# LED_Array.net
KiCad netlist of a schematic drawn in EAGLE
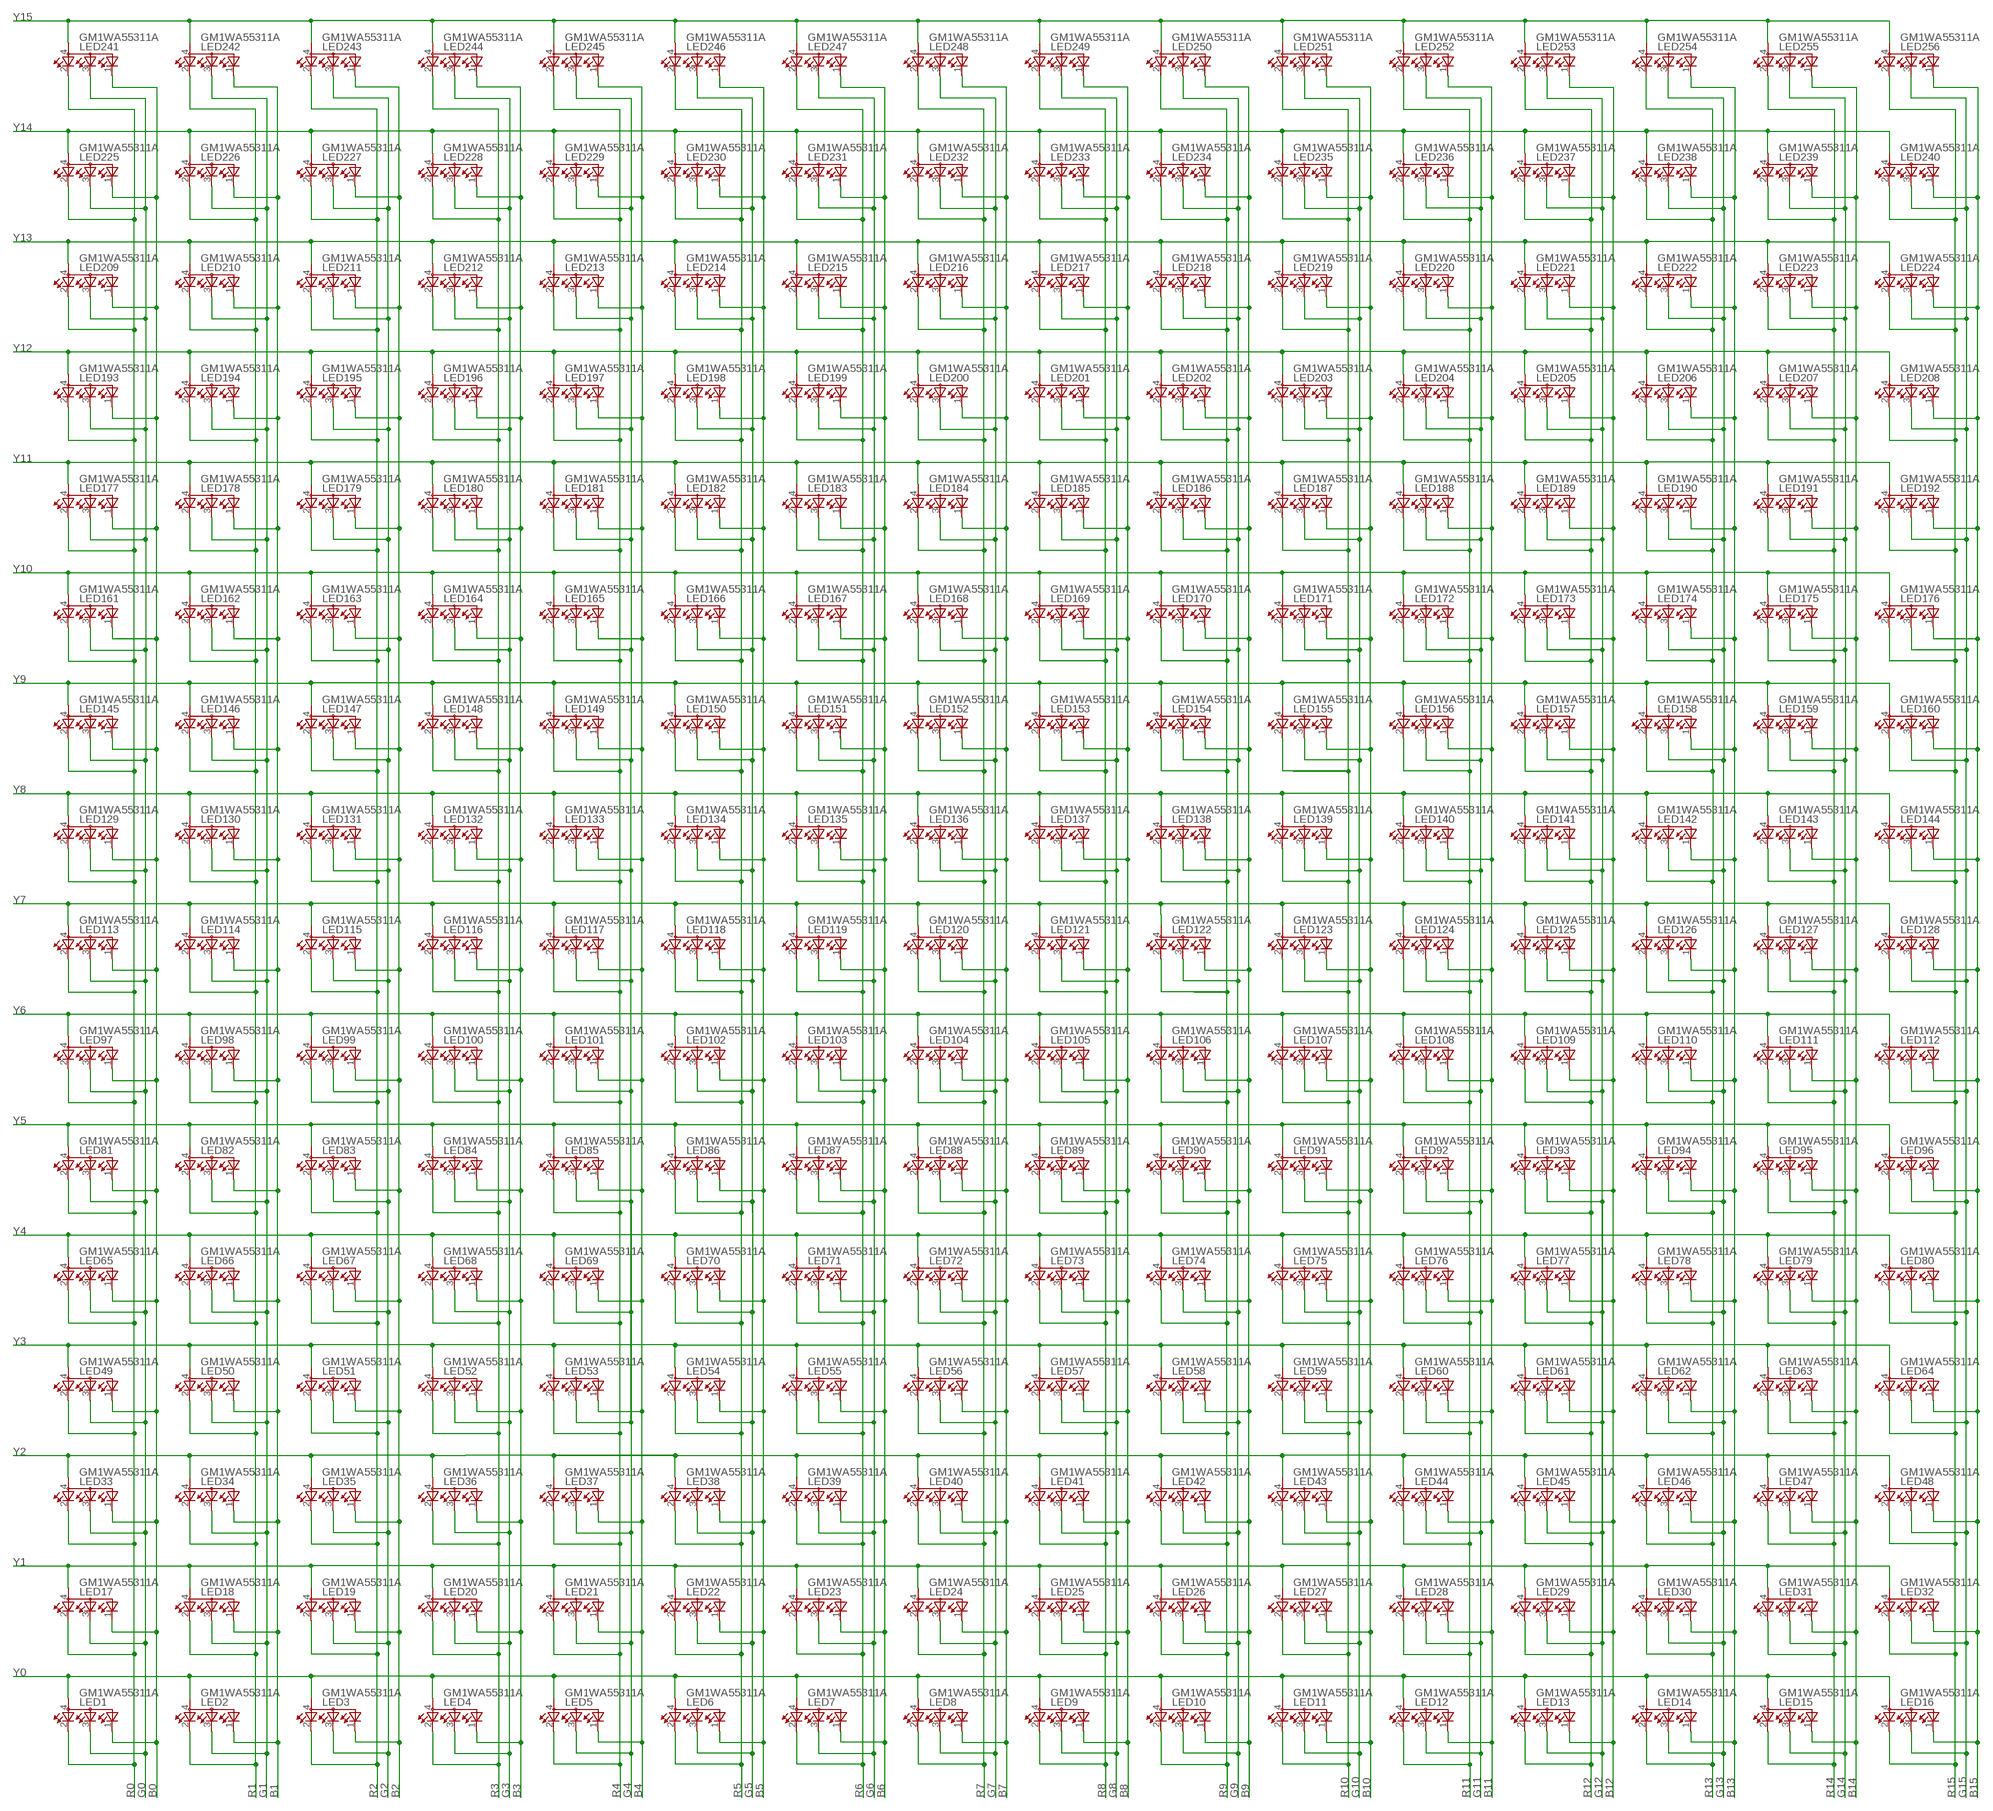
[diagram p0: schematic, sheet 1]

(export (version "E")
  (design (tool "Eeschema 10.0.6"))
  (components
    (comp (ref "LED1")
      (value "GM1WA55311A")
      (footprint "eagle-import:GM1WA55311A")
      (libsource (lib "eagle-import") (part "GM1WA55311A"))
    )
    (comp (ref "LED2")
      (value "GM1WA55311A")
      (footprint "eagle-import:GM1WA55311A")
      (libsource (lib "eagle-import") (part "GM1WA55311A"))
    )
    (comp (ref "LED3")
      (value "GM1WA55311A")
      (footprint "eagle-import:GM1WA55311A")
      (libsource (lib "eagle-import") (part "GM1WA55311A"))
    )
    (comp (ref "LED4")
      (value "GM1WA55311A")
      (footprint "eagle-import:GM1WA55311A")
      (libsource (lib "eagle-import") (part "GM1WA55311A"))
    )
    (comp (ref "LED5")
      (value "GM1WA55311A")
      (footprint "eagle-import:GM1WA55311A")
      (libsource (lib "eagle-import") (part "GM1WA55311A"))
    )
    (comp (ref "LED6")
      (value "GM1WA55311A")
      (footprint "eagle-import:GM1WA55311A")
      (libsource (lib "eagle-import") (part "GM1WA55311A"))
    )
    (comp (ref "LED7")
      (value "GM1WA55311A")
      (footprint "eagle-import:GM1WA55311A")
      (libsource (lib "eagle-import") (part "GM1WA55311A"))
    )
    (comp (ref "LED8")
      (value "GM1WA55311A")
      (footprint "eagle-import:GM1WA55311A")
      (libsource (lib "eagle-import") (part "GM1WA55311A"))
    )
    (comp (ref "LED9")
      (value "GM1WA55311A")
      (footprint "eagle-import:GM1WA55311A")
      (libsource (lib "eagle-import") (part "GM1WA55311A"))
    )
    (comp (ref "LED10")
      (value "GM1WA55311A")
      (footprint "eagle-import:GM1WA55311A")
      (libsource (lib "eagle-import") (part "GM1WA55311A"))
    )
    (comp (ref "LED11")
      (value "GM1WA55311A")
      (footprint "eagle-import:GM1WA55311A")
      (libsource (lib "eagle-import") (part "GM1WA55311A"))
    )
    (comp (ref "LED12")
      (value "GM1WA55311A")
      (footprint "eagle-import:GM1WA55311A")
      (libsource (lib "eagle-import") (part "GM1WA55311A"))
    )
    (comp (ref "LED13")
      (value "GM1WA55311A")
      (footprint "eagle-import:GM1WA55311A")
      (libsource (lib "eagle-import") (part "GM1WA55311A"))
    )
    (comp (ref "LED14")
      (value "GM1WA55311A")
      (footprint "eagle-import:GM1WA55311A")
      (libsource (lib "eagle-import") (part "GM1WA55311A"))
    )
    (comp (ref "LED15")
      (value "GM1WA55311A")
      (footprint "eagle-import:GM1WA55311A")
      (libsource (lib "eagle-import") (part "GM1WA55311A"))
    )
    (comp (ref "LED16")
      (value "GM1WA55311A")
      (footprint "eagle-import:GM1WA55311A")
      (libsource (lib "eagle-import") (part "GM1WA55311A"))
    )
    (comp (ref "LED17")
      (value "GM1WA55311A")
      (footprint "eagle-import:GM1WA55311A")
      (libsource (lib "eagle-import") (part "GM1WA55311A"))
    )
    (comp (ref "LED18")
      (value "GM1WA55311A")
      (footprint "eagle-import:GM1WA55311A")
      (libsource (lib "eagle-import") (part "GM1WA55311A"))
    )
    (comp (ref "LED19")
      (value "GM1WA55311A")
      (footprint "eagle-import:GM1WA55311A")
      (libsource (lib "eagle-import") (part "GM1WA55311A"))
    )
    (comp (ref "LED20")
      (value "GM1WA55311A")
      (footprint "eagle-import:GM1WA55311A")
      (libsource (lib "eagle-import") (part "GM1WA55311A"))
    )
    (comp (ref "LED21")
      (value "GM1WA55311A")
      (footprint "eagle-import:GM1WA55311A")
      (libsource (lib "eagle-import") (part "GM1WA55311A"))
    )
    (comp (ref "LED22")
      (value "GM1WA55311A")
      (footprint "eagle-import:GM1WA55311A")
      (libsource (lib "eagle-import") (part "GM1WA55311A"))
    )
    (comp (ref "LED23")
      (value "GM1WA55311A")
      (footprint "eagle-import:GM1WA55311A")
      (libsource (lib "eagle-import") (part "GM1WA55311A"))
    )
    (comp (ref "LED24")
      (value "GM1WA55311A")
      (footprint "eagle-import:GM1WA55311A")
      (libsource (lib "eagle-import") (part "GM1WA55311A"))
    )
    (comp (ref "LED25")
      (value "GM1WA55311A")
      (footprint "eagle-import:GM1WA55311A")
      (libsource (lib "eagle-import") (part "GM1WA55311A"))
    )
    (comp (ref "LED26")
      (value "GM1WA55311A")
      (footprint "eagle-import:GM1WA55311A")
      (libsource (lib "eagle-import") (part "GM1WA55311A"))
    )
    (comp (ref "LED27")
      (value "GM1WA55311A")
      (footprint "eagle-import:GM1WA55311A")
      (libsource (lib "eagle-import") (part "GM1WA55311A"))
    )
    (comp (ref "LED28")
      (value "GM1WA55311A")
      (footprint "eagle-import:GM1WA55311A")
      (libsource (lib "eagle-import") (part "GM1WA55311A"))
    )
    (comp (ref "LED29")
      (value "GM1WA55311A")
      (footprint "eagle-import:GM1WA55311A")
      (libsource (lib "eagle-import") (part "GM1WA55311A"))
    )
    (comp (ref "LED30")
      (value "GM1WA55311A")
      (footprint "eagle-import:GM1WA55311A")
      (libsource (lib "eagle-import") (part "GM1WA55311A"))
    )
    (comp (ref "LED31")
      (value "GM1WA55311A")
      (footprint "eagle-import:GM1WA55311A")
      (libsource (lib "eagle-import") (part "GM1WA55311A"))
    )
    (comp (ref "LED32")
      (value "GM1WA55311A")
      (footprint "eagle-import:GM1WA55311A")
      (libsource (lib "eagle-import") (part "GM1WA55311A"))
    )
    (comp (ref "LED33")
      (value "GM1WA55311A")
      (footprint "eagle-import:GM1WA55311A")
      (libsource (lib "eagle-import") (part "GM1WA55311A"))
    )
    (comp (ref "LED34")
      (value "GM1WA55311A")
      (footprint "eagle-import:GM1WA55311A")
      (libsource (lib "eagle-import") (part "GM1WA55311A"))
    )
    (comp (ref "LED35")
      (value "GM1WA55311A")
      (footprint "eagle-import:GM1WA55311A")
      (libsource (lib "eagle-import") (part "GM1WA55311A"))
    )
    (comp (ref "LED36")
      (value "GM1WA55311A")
      (footprint "eagle-import:GM1WA55311A")
      (libsource (lib "eagle-import") (part "GM1WA55311A"))
    )
    (comp (ref "LED37")
      (value "GM1WA55311A")
      (footprint "eagle-import:GM1WA55311A")
      (libsource (lib "eagle-import") (part "GM1WA55311A"))
    )
    (comp (ref "LED38")
      (value "GM1WA55311A")
      (footprint "eagle-import:GM1WA55311A")
      (libsource (lib "eagle-import") (part "GM1WA55311A"))
    )
    (comp (ref "LED39")
      (value "GM1WA55311A")
      (footprint "eagle-import:GM1WA55311A")
      (libsource (lib "eagle-import") (part "GM1WA55311A"))
    )
    (comp (ref "LED40")
      (value "GM1WA55311A")
      (footprint "eagle-import:GM1WA55311A")
      (libsource (lib "eagle-import") (part "GM1WA55311A"))
    )
    (comp (ref "LED41")
      (value "GM1WA55311A")
      (footprint "eagle-import:GM1WA55311A")
      (libsource (lib "eagle-import") (part "GM1WA55311A"))
    )
    (comp (ref "LED42")
      (value "GM1WA55311A")
      (footprint "eagle-import:GM1WA55311A")
      (libsource (lib "eagle-import") (part "GM1WA55311A"))
    )
    (comp (ref "LED43")
      (value "GM1WA55311A")
      (footprint "eagle-import:GM1WA55311A")
      (libsource (lib "eagle-import") (part "GM1WA55311A"))
    )
    (comp (ref "LED44")
      (value "GM1WA55311A")
      (footprint "eagle-import:GM1WA55311A")
      (libsource (lib "eagle-import") (part "GM1WA55311A"))
    )
    (comp (ref "LED45")
      (value "GM1WA55311A")
      (footprint "eagle-import:GM1WA55311A")
      (libsource (lib "eagle-import") (part "GM1WA55311A"))
    )
    (comp (ref "LED46")
      (value "GM1WA55311A")
      (footprint "eagle-import:GM1WA55311A")
      (libsource (lib "eagle-import") (part "GM1WA55311A"))
    )
    (comp (ref "LED47")
      (value "GM1WA55311A")
      (footprint "eagle-import:GM1WA55311A")
      (libsource (lib "eagle-import") (part "GM1WA55311A"))
    )
    (comp (ref "LED48")
      (value "GM1WA55311A")
      (footprint "eagle-import:GM1WA55311A")
      (libsource (lib "eagle-import") (part "GM1WA55311A"))
    )
    (comp (ref "LED49")
      (value "GM1WA55311A")
      (footprint "eagle-import:GM1WA55311A")
      (libsource (lib "eagle-import") (part "GM1WA55311A"))
    )
    (comp (ref "LED50")
      (value "GM1WA55311A")
      (footprint "eagle-import:GM1WA55311A")
      (libsource (lib "eagle-import") (part "GM1WA55311A"))
    )
    (comp (ref "LED51")
      (value "GM1WA55311A")
      (footprint "eagle-import:GM1WA55311A")
      (libsource (lib "eagle-import") (part "GM1WA55311A"))
    )
    (comp (ref "LED52")
      (value "GM1WA55311A")
      (footprint "eagle-import:GM1WA55311A")
      (libsource (lib "eagle-import") (part "GM1WA55311A"))
    )
    (comp (ref "LED53")
      (value "GM1WA55311A")
      (footprint "eagle-import:GM1WA55311A")
      (libsource (lib "eagle-import") (part "GM1WA55311A"))
    )
    (comp (ref "LED54")
      (value "GM1WA55311A")
      (footprint "eagle-import:GM1WA55311A")
      (libsource (lib "eagle-import") (part "GM1WA55311A"))
    )
    (comp (ref "LED55")
      (value "GM1WA55311A")
      (footprint "eagle-import:GM1WA55311A")
      (libsource (lib "eagle-import") (part "GM1WA55311A"))
    )
    (comp (ref "LED56")
      (value "GM1WA55311A")
      (footprint "eagle-import:GM1WA55311A")
      (libsource (lib "eagle-import") (part "GM1WA55311A"))
    )
    (comp (ref "LED57")
      (value "GM1WA55311A")
      (footprint "eagle-import:GM1WA55311A")
      (libsource (lib "eagle-import") (part "GM1WA55311A"))
    )
    (comp (ref "LED58")
      (value "GM1WA55311A")
      (footprint "eagle-import:GM1WA55311A")
      (libsource (lib "eagle-import") (part "GM1WA55311A"))
    )
    (comp (ref "LED59")
      (value "GM1WA55311A")
      (footprint "eagle-import:GM1WA55311A")
      (libsource (lib "eagle-import") (part "GM1WA55311A"))
    )
    (comp (ref "LED60")
      (value "GM1WA55311A")
      (footprint "eagle-import:GM1WA55311A")
      (libsource (lib "eagle-import") (part "GM1WA55311A"))
    )
    (comp (ref "LED61")
      (value "GM1WA55311A")
      (footprint "eagle-import:GM1WA55311A")
      (libsource (lib "eagle-import") (part "GM1WA55311A"))
    )
    (comp (ref "LED62")
      (value "GM1WA55311A")
      (footprint "eagle-import:GM1WA55311A")
      (libsource (lib "eagle-import") (part "GM1WA55311A"))
    )
    (comp (ref "LED63")
      (value "GM1WA55311A")
      (footprint "eagle-import:GM1WA55311A")
      (libsource (lib "eagle-import") (part "GM1WA55311A"))
    )
    (comp (ref "LED64")
      (value "GM1WA55311A")
      (footprint "eagle-import:GM1WA55311A")
      (libsource (lib "eagle-import") (part "GM1WA55311A"))
    )
    (comp (ref "LED65")
      (value "GM1WA55311A")
      (footprint "eagle-import:GM1WA55311A")
      (libsource (lib "eagle-import") (part "GM1WA55311A"))
    )
    (comp (ref "LED66")
      (value "GM1WA55311A")
      (footprint "eagle-import:GM1WA55311A")
      (libsource (lib "eagle-import") (part "GM1WA55311A"))
    )
    (comp (ref "LED67")
      (value "GM1WA55311A")
      (footprint "eagle-import:GM1WA55311A")
      (libsource (lib "eagle-import") (part "GM1WA55311A"))
    )
    (comp (ref "LED68")
      (value "GM1WA55311A")
      (footprint "eagle-import:GM1WA55311A")
      (libsource (lib "eagle-import") (part "GM1WA55311A"))
    )
    (comp (ref "LED69")
      (value "GM1WA55311A")
      (footprint "eagle-import:GM1WA55311A")
      (libsource (lib "eagle-import") (part "GM1WA55311A"))
    )
    (comp (ref "LED70")
      (value "GM1WA55311A")
      (footprint "eagle-import:GM1WA55311A")
      (libsource (lib "eagle-import") (part "GM1WA55311A"))
    )
    (comp (ref "LED71")
      (value "GM1WA55311A")
      (footprint "eagle-import:GM1WA55311A")
      (libsource (lib "eagle-import") (part "GM1WA55311A"))
    )
    (comp (ref "LED72")
      (value "GM1WA55311A")
      (footprint "eagle-import:GM1WA55311A")
      (libsource (lib "eagle-import") (part "GM1WA55311A"))
    )
    (comp (ref "LED73")
      (value "GM1WA55311A")
      (footprint "eagle-import:GM1WA55311A")
      (libsource (lib "eagle-import") (part "GM1WA55311A"))
    )
    (comp (ref "LED74")
      (value "GM1WA55311A")
      (footprint "eagle-import:GM1WA55311A")
      (libsource (lib "eagle-import") (part "GM1WA55311A"))
    )
    (comp (ref "LED75")
      (value "GM1WA55311A")
      (footprint "eagle-import:GM1WA55311A")
      (libsource (lib "eagle-import") (part "GM1WA55311A"))
    )
    (comp (ref "LED76")
      (value "GM1WA55311A")
      (footprint "eagle-import:GM1WA55311A")
      (libsource (lib "eagle-import") (part "GM1WA55311A"))
    )
    (comp (ref "LED77")
      (value "GM1WA55311A")
      (footprint "eagle-import:GM1WA55311A")
      (libsource (lib "eagle-import") (part "GM1WA55311A"))
    )
    (comp (ref "LED78")
      (value "GM1WA55311A")
      (footprint "eagle-import:GM1WA55311A")
      (libsource (lib "eagle-import") (part "GM1WA55311A"))
    )
    (comp (ref "LED79")
      (value "GM1WA55311A")
      (footprint "eagle-import:GM1WA55311A")
      (libsource (lib "eagle-import") (part "GM1WA55311A"))
    )
    (comp (ref "LED80")
      (value "GM1WA55311A")
      (footprint "eagle-import:GM1WA55311A")
      (libsource (lib "eagle-import") (part "GM1WA55311A"))
    )
    (comp (ref "LED81")
      (value "GM1WA55311A")
      (footprint "eagle-import:GM1WA55311A")
      (libsource (lib "eagle-import") (part "GM1WA55311A"))
    )
    (comp (ref "LED82")
      (value "GM1WA55311A")
      (footprint "eagle-import:GM1WA55311A")
      (libsource (lib "eagle-import") (part "GM1WA55311A"))
    )
    (comp (ref "LED83")
      (value "GM1WA55311A")
      (footprint "eagle-import:GM1WA55311A")
      (libsource (lib "eagle-import") (part "GM1WA55311A"))
    )
    (comp (ref "LED84")
      (value "GM1WA55311A")
      (footprint "eagle-import:GM1WA55311A")
      (libsource (lib "eagle-import") (part "GM1WA55311A"))
    )
    (comp (ref "LED85")
      (value "GM1WA55311A")
      (footprint "eagle-import:GM1WA55311A")
      (libsource (lib "eagle-import") (part "GM1WA55311A"))
    )
    (comp (ref "LED86")
      (value "GM1WA55311A")
      (footprint "eagle-import:GM1WA55311A")
      (libsource (lib "eagle-import") (part "GM1WA55311A"))
    )
    (comp (ref "LED87")
      (value "GM1WA55311A")
      (footprint "eagle-import:GM1WA55311A")
      (libsource (lib "eagle-import") (part "GM1WA55311A"))
    )
    (comp (ref "LED88")
      (value "GM1WA55311A")
      (footprint "eagle-import:GM1WA55311A")
      (libsource (lib "eagle-import") (part "GM1WA55311A"))
    )
    (comp (ref "LED89")
      (value "GM1WA55311A")
      (footprint "eagle-import:GM1WA55311A")
      (libsource (lib "eagle-import") (part "GM1WA55311A"))
    )
    (comp (ref "LED90")
      (value "GM1WA55311A")
      (footprint "eagle-import:GM1WA55311A")
      (libsource (lib "eagle-import") (part "GM1WA55311A"))
    )
    (comp (ref "LED91")
      (value "GM1WA55311A")
      (footprint "eagle-import:GM1WA55311A")
      (libsource (lib "eagle-import") (part "GM1WA55311A"))
    )
    (comp (ref "LED92")
      (value "GM1WA55311A")
      (footprint "eagle-import:GM1WA55311A")
      (libsource (lib "eagle-import") (part "GM1WA55311A"))
    )
    (comp (ref "LED93")
      (value "GM1WA55311A")
      (footprint "eagle-import:GM1WA55311A")
      (libsource (lib "eagle-import") (part "GM1WA55311A"))
    )
    (comp (ref "LED94")
      (value "GM1WA55311A")
      (footprint "eagle-import:GM1WA55311A")
      (libsource (lib "eagle-import") (part "GM1WA55311A"))
    )
    (comp (ref "LED95")
      (value "GM1WA55311A")
      (footprint "eagle-import:GM1WA55311A")
      (libsource (lib "eagle-import") (part "GM1WA55311A"))
    )
    (comp (ref "LED96")
      (value "GM1WA55311A")
      (footprint "eagle-import:GM1WA55311A")
      (libsource (lib "eagle-import") (part "GM1WA55311A"))
    )
    (comp (ref "LED97")
      (value "GM1WA55311A")
      (footprint "eagle-import:GM1WA55311A")
      (libsource (lib "eagle-import") (part "GM1WA55311A"))
    )
    (comp (ref "LED98")
      (value "GM1WA55311A")
      (footprint "eagle-import:GM1WA55311A")
      (libsource (lib "eagle-import") (part "GM1WA55311A"))
    )
    (comp (ref "LED99")
      (value "GM1WA55311A")
      (footprint "eagle-import:GM1WA55311A")
      (libsource (lib "eagle-import") (part "GM1WA55311A"))
    )
    (comp (ref "LED100")
      (value "GM1WA55311A")
      (footprint "eagle-import:GM1WA55311A")
      (libsource (lib "eagle-import") (part "GM1WA55311A"))
    )
    (comp (ref "LED101")
      (value "GM1WA55311A")
      (footprint "eagle-import:GM1WA55311A")
      (libsource (lib "eagle-import") (part "GM1WA55311A"))
    )
    (comp (ref "LED102")
      (value "GM1WA55311A")
      (footprint "eagle-import:GM1WA55311A")
      (libsource (lib "eagle-import") (part "GM1WA55311A"))
    )
    (comp (ref "LED103")
      (value "GM1WA55311A")
      (footprint "eagle-import:GM1WA55311A")
      (libsource (lib "eagle-import") (part "GM1WA55311A"))
    )
    (comp (ref "LED104")
      (value "GM1WA55311A")
      (footprint "eagle-import:GM1WA55311A")
      (libsource (lib "eagle-import") (part "GM1WA55311A"))
    )
    (comp (ref "LED105")
      (value "GM1WA55311A")
      (footprint "eagle-import:GM1WA55311A")
      (libsource (lib "eagle-import") (part "GM1WA55311A"))
    )
    (comp (ref "LED106")
      (value "GM1WA55311A")
      (footprint "eagle-import:GM1WA55311A")
      (libsource (lib "eagle-import") (part "GM1WA55311A"))
    )
    (comp (ref "LED107")
      (value "GM1WA55311A")
      (footprint "eagle-import:GM1WA55311A")
      (libsource (lib "eagle-import") (part "GM1WA55311A"))
    )
    (comp (ref "LED108")
      (value "GM1WA55311A")
      (footprint "eagle-import:GM1WA55311A")
      (libsource (lib "eagle-import") (part "GM1WA55311A"))
    )
    (comp (ref "LED109")
      (value "GM1WA55311A")
      (footprint "eagle-import:GM1WA55311A")
      (libsource (lib "eagle-import") (part "GM1WA55311A"))
    )
    (comp (ref "LED110")
      (value "GM1WA55311A")
      (footprint "eagle-import:GM1WA55311A")
      (libsource (lib "eagle-import") (part "GM1WA55311A"))
    )
    (comp (ref "LED111")
      (value "GM1WA55311A")
      (footprint "eagle-import:GM1WA55311A")
      (libsource (lib "eagle-import") (part "GM1WA55311A"))
    )
    (comp (ref "LED112")
      (value "GM1WA55311A")
      (footprint "eagle-import:GM1WA55311A")
      (libsource (lib "eagle-import") (part "GM1WA55311A"))
    )
    (comp (ref "LED113")
      (value "GM1WA55311A")
      (footprint "eagle-import:GM1WA55311A")
      (libsource (lib "eagle-import") (part "GM1WA55311A"))
    )
    (comp (ref "LED114")
      (value "GM1WA55311A")
      (footprint "eagle-import:GM1WA55311A")
      (libsource (lib "eagle-import") (part "GM1WA55311A"))
    )
    (comp (ref "LED115")
      (value "GM1WA55311A")
      (footprint "eagle-import:GM1WA55311A")
      (libsource (lib "eagle-import") (part "GM1WA55311A"))
    )
    (comp (ref "LED116")
      (value "GM1WA55311A")
      (footprint "eagle-import:GM1WA55311A")
      (libsource (lib "eagle-import") (part "GM1WA55311A"))
    )
    (comp (ref "LED117")
      (value "GM1WA55311A")
      (footprint "eagle-import:GM1WA55311A")
      (libsource (lib "eagle-import") (part "GM1WA55311A"))
    )
    (comp (ref "LED118")
      (value "GM1WA55311A")
      (footprint "eagle-import:GM1WA55311A")
      (libsource (lib "eagle-import") (part "GM1WA55311A"))
    )
    (comp (ref "LED119")
      (value "GM1WA55311A")
      (footprint "eagle-import:GM1WA55311A")
      (libsource (lib "eagle-import") (part "GM1WA55311A"))
    )
    (comp (ref "LED120")
      (value "GM1WA55311A")
      (footprint "eagle-import:GM1WA55311A")
      (libsource (lib "eagle-import") (part "GM1WA55311A"))
    )
    (comp (ref "LED121")
      (value "GM1WA55311A")
      (footprint "eagle-import:GM1WA55311A")
      (libsource (lib "eagle-import") (part "GM1WA55311A"))
    )
    (comp (ref "LED122")
      (value "GM1WA55311A")
      (footprint "eagle-import:GM1WA55311A")
      (libsource (lib "eagle-import") (part "GM1WA55311A"))
    )
    (comp (ref "LED123")
      (value "GM1WA55311A")
      (footprint "eagle-import:GM1WA55311A")
      (libsource (lib "eagle-import") (part "GM1WA55311A"))
    )
    (comp (ref "LED124")
      (value "GM1WA55311A")
      (footprint "eagle-import:GM1WA55311A")
      (libsource (lib "eagle-import") (part "GM1WA55311A"))
    )
    (comp (ref "LED125")
      (value "GM1WA55311A")
      (footprint "eagle-import:GM1WA55311A")
      (libsource (lib "eagle-import") (part "GM1WA55311A"))
    )
    (comp (ref "LED126")
      (value "GM1WA55311A")
      (footprint "eagle-import:GM1WA55311A")
      (libsource (lib "eagle-import") (part "GM1WA55311A"))
    )
    (comp (ref "LED127")
      (value "GM1WA55311A")
      (footprint "eagle-import:GM1WA55311A")
      (libsource (lib "eagle-import") (part "GM1WA55311A"))
    )
    (comp (ref "LED128")
      (value "GM1WA55311A")
      (footprint "eagle-import:GM1WA55311A")
      (libsource (lib "eagle-import") (part "GM1WA55311A"))
    )
    (comp (ref "LED129")
      (value "GM1WA55311A")
      (footprint "eagle-import:GM1WA55311A")
      (libsource (lib "eagle-import") (part "GM1WA55311A"))
    )
    (comp (ref "LED130")
      (value "GM1WA55311A")
      (footprint "eagle-import:GM1WA55311A")
      (libsource (lib "eagle-import") (part "GM1WA55311A"))
    )
    (comp (ref "LED131")
      (value "GM1WA55311A")
      (footprint "eagle-import:GM1WA55311A")
      (libsource (lib "eagle-import") (part "GM1WA55311A"))
    )
    (comp (ref "LED132")
      (value "GM1WA55311A")
      (footprint "eagle-import:GM1WA55311A")
      (libsource (lib "eagle-import") (part "GM1WA55311A"))
    )
    (comp (ref "LED133")
      (value "GM1WA55311A")
      (footprint "eagle-import:GM1WA55311A")
      (libsource (lib "eagle-import") (part "GM1WA55311A"))
    )
    (comp (ref "LED134")
      (value "GM1WA55311A")
      (footprint "eagle-import:GM1WA55311A")
      (libsource (lib "eagle-import") (part "GM1WA55311A"))
    )
    (comp (ref "LED135")
      (value "GM1WA55311A")
      (footprint "eagle-import:GM1WA55311A")
      (libsource (lib "eagle-import") (part "GM1WA55311A"))
    )
    (comp (ref "LED136")
      (value "GM1WA55311A")
      (footprint "eagle-import:GM1WA55311A")
      (libsource (lib "eagle-import") (part "GM1WA55311A"))
    )
    (comp (ref "LED137")
      (value "GM1WA55311A")
      (footprint "eagle-import:GM1WA55311A")
      (libsource (lib "eagle-import") (part "GM1WA55311A"))
    )
    (comp (ref "LED138")
      (value "GM1WA55311A")
      (footprint "eagle-import:GM1WA55311A")
      (libsource (lib "eagle-import") (part "GM1WA55311A"))
    )
    (comp (ref "LED139")
      (value "GM1WA55311A")
      (footprint "eagle-import:GM1WA55311A")
      (libsource (lib "eagle-import") (part "GM1WA55311A"))
    )
    (comp (ref "LED140")
      (value "GM1WA55311A")
      (footprint "eagle-import:GM1WA55311A")
      (libsource (lib "eagle-import") (part "GM1WA55311A"))
    )
    (comp (ref "LED141")
      (value "GM1WA55311A")
      (footprint "eagle-import:GM1WA55311A")
      (libsource (lib "eagle-import") (part "GM1WA55311A"))
    )
    (comp (ref "LED142")
      (value "GM1WA55311A")
      (footprint "eagle-import:GM1WA55311A")
      (libsource (lib "eagle-import") (part "GM1WA55311A"))
    )
    (comp (ref "LED143")
      (value "GM1WA55311A")
      (footprint "eagle-import:GM1WA55311A")
      (libsource (lib "eagle-import") (part "GM1WA55311A"))
    )
    (comp (ref "LED144")
      (value "GM1WA55311A")
      (footprint "eagle-import:GM1WA55311A")
      (libsource (lib "eagle-import") (part "GM1WA55311A"))
    )
    (comp (ref "LED145")
      (value "GM1WA55311A")
      (footprint "eagle-import:GM1WA55311A")
      (libsource (lib "eagle-import") (part "GM1WA55311A"))
    )
    (comp (ref "LED146")
      (value "GM1WA55311A")
      (footprint "eagle-import:GM1WA55311A")
      (libsource (lib "eagle-import") (part "GM1WA55311A"))
    )
    (comp (ref "LED147")
      (value "GM1WA55311A")
      (footprint "eagle-import:GM1WA55311A")
      (libsource (lib "eagle-import") (part "GM1WA55311A"))
    )
    (comp (ref "LED148")
      (value "GM1WA55311A")
      (footprint "eagle-import:GM1WA55311A")
      (libsource (lib "eagle-import") (part "GM1WA55311A"))
    )
    (comp (ref "LED149")
      (value "GM1WA55311A")
      (footprint "eagle-import:GM1WA55311A")
      (libsource (lib "eagle-import") (part "GM1WA55311A"))
    )
    (comp (ref "LED150")
      (value "GM1WA55311A")
      (footprint "eagle-import:GM1WA55311A")
      (libsource (lib "eagle-import") (part "GM1WA55311A"))
    )
    (comp (ref "LED151")
      (value "GM1WA55311A")
      (footprint "eagle-import:GM1WA55311A")
      (libsource (lib "eagle-import") (part "GM1WA55311A"))
    )
    (comp (ref "LED152")
      (value "GM1WA55311A")
      (footprint "eagle-import:GM1WA55311A")
      (libsource (lib "eagle-import") (part "GM1WA55311A"))
    )
    (comp (ref "LED153")
      (value "GM1WA55311A")
      (footprint "eagle-import:GM1WA55311A")
      (libsource (lib "eagle-import") (part "GM1WA55311A"))
    )
    (comp (ref "LED154")
      (value "GM1WA55311A")
      (footprint "eagle-import:GM1WA55311A")
      (libsource (lib "eagle-import") (part "GM1WA55311A"))
    )
    (comp (ref "LED155")
      (value "GM1WA55311A")
      (footprint "eagle-import:GM1WA55311A")
      (libsource (lib "eagle-import") (part "GM1WA55311A"))
    )
    (comp (ref "LED156")
      (value "GM1WA55311A")
      (footprint "eagle-import:GM1WA55311A")
      (libsource (lib "eagle-import") (part "GM1WA55311A"))
    )
    (comp (ref "LED157")
      (value "GM1WA55311A")
      (footprint "eagle-import:GM1WA55311A")
      (libsource (lib "eagle-import") (part "GM1WA55311A"))
    )
    (comp (ref "LED158")
      (value "GM1WA55311A")
      (footprint "eagle-import:GM1WA55311A")
      (libsource (lib "eagle-import") (part "GM1WA55311A"))
    )
    (comp (ref "LED159")
      (value "GM1WA55311A")
      (footprint "eagle-import:GM1WA55311A")
      (libsource (lib "eagle-import") (part "GM1WA55311A"))
    )
    (comp (ref "LED160")
      (value "GM1WA55311A")
      (footprint "eagle-import:GM1WA55311A")
      (libsource (lib "eagle-import") (part "GM1WA55311A"))
    )
    (comp (ref "LED161")
      (value "GM1WA55311A")
      (footprint "eagle-import:GM1WA55311A")
      (libsource (lib "eagle-import") (part "GM1WA55311A"))
    )
    (comp (ref "LED162")
      (value "GM1WA55311A")
      (footprint "eagle-import:GM1WA55311A")
      (libsource (lib "eagle-import") (part "GM1WA55311A"))
    )
    (comp (ref "LED163")
      (value "GM1WA55311A")
      (footprint "eagle-import:GM1WA55311A")
      (libsource (lib "eagle-import") (part "GM1WA55311A"))
    )
    (comp (ref "LED164")
      (value "GM1WA55311A")
      (footprint "eagle-import:GM1WA55311A")
      (libsource (lib "eagle-import") (part "GM1WA55311A"))
    )
    (comp (ref "LED165")
      (value "GM1WA55311A")
      (footprint "eagle-import:GM1WA55311A")
      (libsource (lib "eagle-import") (part "GM1WA55311A"))
    )
    (comp (ref "LED166")
      (value "GM1WA55311A")
      (footprint "eagle-import:GM1WA55311A")
      (libsource (lib "eagle-import") (part "GM1WA55311A"))
    )
    (comp (ref "LED167")
      (value "GM1WA55311A")
      (footprint "eagle-import:GM1WA55311A")
      (libsource (lib "eagle-import") (part "GM1WA55311A"))
    )
    (comp (ref "LED168")
      (value "GM1WA55311A")
      (footprint "eagle-import:GM1WA55311A")
      (libsource (lib "eagle-import") (part "GM1WA55311A"))
    )
    (comp (ref "LED169")
      (value "GM1WA55311A")
      (footprint "eagle-import:GM1WA55311A")
      (libsource (lib "eagle-import") (part "GM1WA55311A"))
    )
    (comp (ref "LED170")
      (value "GM1WA55311A")
      (footprint "eagle-import:GM1WA55311A")
      (libsource (lib "eagle-import") (part "GM1WA55311A"))
    )
    (comp (ref "LED171")
      (value "GM1WA55311A")
      (footprint "eagle-import:GM1WA55311A")
      (libsource (lib "eagle-import") (part "GM1WA55311A"))
    )
    (comp (ref "LED172")
      (value "GM1WA55311A")
      (footprint "eagle-import:GM1WA55311A")
      (libsource (lib "eagle-import") (part "GM1WA55311A"))
    )
    (comp (ref "LED173")
      (value "GM1WA55311A")
      (footprint "eagle-import:GM1WA55311A")
      (libsource (lib "eagle-import") (part "GM1WA55311A"))
    )
    (comp (ref "LED174")
      (value "GM1WA55311A")
      (footprint "eagle-import:GM1WA55311A")
      (libsource (lib "eagle-import") (part "GM1WA55311A"))
    )
    (comp (ref "LED175")
      (value "GM1WA55311A")
      (footprint "eagle-import:GM1WA55311A")
      (libsource (lib "eagle-import") (part "GM1WA55311A"))
    )
    (comp (ref "LED176")
      (value "GM1WA55311A")
      (footprint "eagle-import:GM1WA55311A")
      (libsource (lib "eagle-import") (part "GM1WA55311A"))
    )
    (comp (ref "LED177")
      (value "GM1WA55311A")
      (footprint "eagle-import:GM1WA55311A")
      (libsource (lib "eagle-import") (part "GM1WA55311A"))
    )
    (comp (ref "LED178")
      (value "GM1WA55311A")
      (footprint "eagle-import:GM1WA55311A")
      (libsource (lib "eagle-import") (part "GM1WA55311A"))
    )
    (comp (ref "LED179")
      (value "GM1WA55311A")
      (footprint "eagle-import:GM1WA55311A")
      (libsource (lib "eagle-import") (part "GM1WA55311A"))
    )
    (comp (ref "LED180")
      (value "GM1WA55311A")
      (footprint "eagle-import:GM1WA55311A")
      (libsource (lib "eagle-import") (part "GM1WA55311A"))
    )
    (comp (ref "LED181")
      (value "GM1WA55311A")
      (footprint "eagle-import:GM1WA55311A")
      (libsource (lib "eagle-import") (part "GM1WA55311A"))
    )
    (comp (ref "LED182")
      (value "GM1WA55311A")
      (footprint "eagle-import:GM1WA55311A")
      (libsource (lib "eagle-import") (part "GM1WA55311A"))
    )
    (comp (ref "LED183")
      (value "GM1WA55311A")
      (footprint "eagle-import:GM1WA55311A")
      (libsource (lib "eagle-import") (part "GM1WA55311A"))
    )
    (comp (ref "LED184")
      (value "GM1WA55311A")
      (footprint "eagle-import:GM1WA55311A")
      (libsource (lib "eagle-import") (part "GM1WA55311A"))
    )
    (comp (ref "LED185")
      (value "GM1WA55311A")
      (footprint "eagle-import:GM1WA55311A")
      (libsource (lib "eagle-import") (part "GM1WA55311A"))
    )
    (comp (ref "LED186")
      (value "GM1WA55311A")
      (footprint "eagle-import:GM1WA55311A")
      (libsource (lib "eagle-import") (part "GM1WA55311A"))
    )
    (comp (ref "LED187")
      (value "GM1WA55311A")
      (footprint "eagle-import:GM1WA55311A")
      (libsource (lib "eagle-import") (part "GM1WA55311A"))
    )
    (comp (ref "LED188")
      (value "GM1WA55311A")
      (footprint "eagle-import:GM1WA55311A")
      (libsource (lib "eagle-import") (part "GM1WA55311A"))
    )
    (comp (ref "LED189")
      (value "GM1WA55311A")
      (footprint "eagle-import:GM1WA55311A")
      (libsource (lib "eagle-import") (part "GM1WA55311A"))
    )
    (comp (ref "LED190")
      (value "GM1WA55311A")
      (footprint "eagle-import:GM1WA55311A")
      (libsource (lib "eagle-import") (part "GM1WA55311A"))
    )
    (comp (ref "LED191")
      (value "GM1WA55311A")
      (footprint "eagle-import:GM1WA55311A")
      (libsource (lib "eagle-import") (part "GM1WA55311A"))
    )
    (comp (ref "LED192")
      (value "GM1WA55311A")
      (footprint "eagle-import:GM1WA55311A")
      (libsource (lib "eagle-import") (part "GM1WA55311A"))
    )
    (comp (ref "LED193")
      (value "GM1WA55311A")
      (footprint "eagle-import:GM1WA55311A")
      (libsource (lib "eagle-import") (part "GM1WA55311A"))
    )
    (comp (ref "LED194")
      (value "GM1WA55311A")
      (footprint "eagle-import:GM1WA55311A")
      (libsource (lib "eagle-import") (part "GM1WA55311A"))
    )
    (comp (ref "LED195")
      (value "GM1WA55311A")
      (footprint "eagle-import:GM1WA55311A")
      (libsource (lib "eagle-import") (part "GM1WA55311A"))
    )
    (comp (ref "LED196")
      (value "GM1WA55311A")
      (footprint "eagle-import:GM1WA55311A")
      (libsource (lib "eagle-import") (part "GM1WA55311A"))
    )
    (comp (ref "LED197")
      (value "GM1WA55311A")
      (footprint "eagle-import:GM1WA55311A")
      (libsource (lib "eagle-import") (part "GM1WA55311A"))
    )
    (comp (ref "LED198")
      (value "GM1WA55311A")
      (footprint "eagle-import:GM1WA55311A")
      (libsource (lib "eagle-import") (part "GM1WA55311A"))
    )
    (comp (ref "LED199")
      (value "GM1WA55311A")
      (footprint "eagle-import:GM1WA55311A")
      (libsource (lib "eagle-import") (part "GM1WA55311A"))
    )
    (comp (ref "LED200")
      (value "GM1WA55311A")
      (footprint "eagle-import:GM1WA55311A")
      (libsource (lib "eagle-import") (part "GM1WA55311A"))
    )
    (comp (ref "LED201")
      (value "GM1WA55311A")
      (footprint "eagle-import:GM1WA55311A")
      (libsource (lib "eagle-import") (part "GM1WA55311A"))
    )
    (comp (ref "LED202")
      (value "GM1WA55311A")
      (footprint "eagle-import:GM1WA55311A")
      (libsource (lib "eagle-import") (part "GM1WA55311A"))
    )
    (comp (ref "LED203")
      (value "GM1WA55311A")
      (footprint "eagle-import:GM1WA55311A")
      (libsource (lib "eagle-import") (part "GM1WA55311A"))
    )
    (comp (ref "LED204")
      (value "GM1WA55311A")
      (footprint "eagle-import:GM1WA55311A")
      (libsource (lib "eagle-import") (part "GM1WA55311A"))
    )
    (comp (ref "LED205")
      (value "GM1WA55311A")
      (footprint "eagle-import:GM1WA55311A")
      (libsource (lib "eagle-import") (part "GM1WA55311A"))
    )
    (comp (ref "LED206")
      (value "GM1WA55311A")
      (footprint "eagle-import:GM1WA55311A")
      (libsource (lib "eagle-import") (part "GM1WA55311A"))
    )
    (comp (ref "LED207")
      (value "GM1WA55311A")
      (footprint "eagle-import:GM1WA55311A")
      (libsource (lib "eagle-import") (part "GM1WA55311A"))
    )
    (comp (ref "LED208")
      (value "GM1WA55311A")
      (footprint "eagle-import:GM1WA55311A")
      (libsource (lib "eagle-import") (part "GM1WA55311A"))
    )
    (comp (ref "LED209")
      (value "GM1WA55311A")
      (footprint "eagle-import:GM1WA55311A")
      (libsource (lib "eagle-import") (part "GM1WA55311A"))
    )
    (comp (ref "LED210")
      (value "GM1WA55311A")
      (footprint "eagle-import:GM1WA55311A")
      (libsource (lib "eagle-import") (part "GM1WA55311A"))
    )
    (comp (ref "LED211")
      (value "GM1WA55311A")
      (footprint "eagle-import:GM1WA55311A")
      (libsource (lib "eagle-import") (part "GM1WA55311A"))
    )
    (comp (ref "LED212")
      (value "GM1WA55311A")
      (footprint "eagle-import:GM1WA55311A")
      (libsource (lib "eagle-import") (part "GM1WA55311A"))
    )
    (comp (ref "LED213")
      (value "GM1WA55311A")
      (footprint "eagle-import:GM1WA55311A")
      (libsource (lib "eagle-import") (part "GM1WA55311A"))
    )
    (comp (ref "LED214")
      (value "GM1WA55311A")
      (footprint "eagle-import:GM1WA55311A")
      (libsource (lib "eagle-import") (part "GM1WA55311A"))
    )
    (comp (ref "LED215")
      (value "GM1WA55311A")
      (footprint "eagle-import:GM1WA55311A")
      (libsource (lib "eagle-import") (part "GM1WA55311A"))
    )
    (comp (ref "LED216")
      (value "GM1WA55311A")
      (footprint "eagle-import:GM1WA55311A")
      (libsource (lib "eagle-import") (part "GM1WA55311A"))
    )
    (comp (ref "LED217")
      (value "GM1WA55311A")
      (footprint "eagle-import:GM1WA55311A")
      (libsource (lib "eagle-import") (part "GM1WA55311A"))
    )
    (comp (ref "LED218")
      (value "GM1WA55311A")
      (footprint "eagle-import:GM1WA55311A")
      (libsource (lib "eagle-import") (part "GM1WA55311A"))
    )
    (comp (ref "LED219")
      (value "GM1WA55311A")
      (footprint "eagle-import:GM1WA55311A")
      (libsource (lib "eagle-import") (part "GM1WA55311A"))
    )
    (comp (ref "LED220")
      (value "GM1WA55311A")
      (footprint "eagle-import:GM1WA55311A")
      (libsource (lib "eagle-import") (part "GM1WA55311A"))
    )
    (comp (ref "LED221")
      (value "GM1WA55311A")
      (footprint "eagle-import:GM1WA55311A")
      (libsource (lib "eagle-import") (part "GM1WA55311A"))
    )
    (comp (ref "LED222")
      (value "GM1WA55311A")
      (footprint "eagle-import:GM1WA55311A")
      (libsource (lib "eagle-import") (part "GM1WA55311A"))
    )
    (comp (ref "LED223")
      (value "GM1WA55311A")
      (footprint "eagle-import:GM1WA55311A")
      (libsource (lib "eagle-import") (part "GM1WA55311A"))
    )
    (comp (ref "LED224")
      (value "GM1WA55311A")
      (footprint "eagle-import:GM1WA55311A")
      (libsource (lib "eagle-import") (part "GM1WA55311A"))
    )
    (comp (ref "LED225")
      (value "GM1WA55311A")
      (footprint "eagle-import:GM1WA55311A")
      (libsource (lib "eagle-import") (part "GM1WA55311A"))
    )
    (comp (ref "LED226")
      (value "GM1WA55311A")
      (footprint "eagle-import:GM1WA55311A")
      (libsource (lib "eagle-import") (part "GM1WA55311A"))
    )
    (comp (ref "LED227")
      (value "GM1WA55311A")
      (footprint "eagle-import:GM1WA55311A")
      (libsource (lib "eagle-import") (part "GM1WA55311A"))
    )
    (comp (ref "LED228")
      (value "GM1WA55311A")
      (footprint "eagle-import:GM1WA55311A")
      (libsource (lib "eagle-import") (part "GM1WA55311A"))
    )
    (comp (ref "LED229")
      (value "GM1WA55311A")
      (footprint "eagle-import:GM1WA55311A")
      (libsource (lib "eagle-import") (part "GM1WA55311A"))
    )
    (comp (ref "LED230")
      (value "GM1WA55311A")
      (footprint "eagle-import:GM1WA55311A")
      (libsource (lib "eagle-import") (part "GM1WA55311A"))
    )
    (comp (ref "LED231")
      (value "GM1WA55311A")
      (footprint "eagle-import:GM1WA55311A")
      (libsource (lib "eagle-import") (part "GM1WA55311A"))
    )
    (comp (ref "LED232")
      (value "GM1WA55311A")
      (footprint "eagle-import:GM1WA55311A")
      (libsource (lib "eagle-import") (part "GM1WA55311A"))
    )
    (comp (ref "LED233")
      (value "GM1WA55311A")
      (footprint "eagle-import:GM1WA55311A")
      (libsource (lib "eagle-import") (part "GM1WA55311A"))
    )
    (comp (ref "LED234")
      (value "GM1WA55311A")
      (footprint "eagle-import:GM1WA55311A")
      (libsource (lib "eagle-import") (part "GM1WA55311A"))
    )
    (comp (ref "LED235")
      (value "GM1WA55311A")
      (footprint "eagle-import:GM1WA55311A")
      (libsource (lib "eagle-import") (part "GM1WA55311A"))
    )
    (comp (ref "LED236")
      (value "GM1WA55311A")
      (footprint "eagle-import:GM1WA55311A")
      (libsource (lib "eagle-import") (part "GM1WA55311A"))
    )
    (comp (ref "LED237")
      (value "GM1WA55311A")
      (footprint "eagle-import:GM1WA55311A")
      (libsource (lib "eagle-import") (part "GM1WA55311A"))
    )
    (comp (ref "LED238")
      (value "GM1WA55311A")
      (footprint "eagle-import:GM1WA55311A")
      (libsource (lib "eagle-import") (part "GM1WA55311A"))
    )
    (comp (ref "LED239")
      (value "GM1WA55311A")
      (footprint "eagle-import:GM1WA55311A")
      (libsource (lib "eagle-import") (part "GM1WA55311A"))
    )
    (comp (ref "LED240")
      (value "GM1WA55311A")
      (footprint "eagle-import:GM1WA55311A")
      (libsource (lib "eagle-import") (part "GM1WA55311A"))
    )
    (comp (ref "LED241")
      (value "GM1WA55311A")
      (footprint "eagle-import:GM1WA55311A")
      (libsource (lib "eagle-import") (part "GM1WA55311A"))
    )
    (comp (ref "LED242")
      (value "GM1WA55311A")
      (footprint "eagle-import:GM1WA55311A")
      (libsource (lib "eagle-import") (part "GM1WA55311A"))
    )
    (comp (ref "LED243")
      (value "GM1WA55311A")
      (footprint "eagle-import:GM1WA55311A")
      (libsource (lib "eagle-import") (part "GM1WA55311A"))
    )
    (comp (ref "LED244")
      (value "GM1WA55311A")
      (footprint "eagle-import:GM1WA55311A")
      (libsource (lib "eagle-import") (part "GM1WA55311A"))
    )
    (comp (ref "LED245")
      (value "GM1WA55311A")
      (footprint "eagle-import:GM1WA55311A")
      (libsource (lib "eagle-import") (part "GM1WA55311A"))
    )
    (comp (ref "LED246")
      (value "GM1WA55311A")
      (footprint "eagle-import:GM1WA55311A")
      (libsource (lib "eagle-import") (part "GM1WA55311A"))
    )
    (comp (ref "LED247")
      (value "GM1WA55311A")
      (footprint "eagle-import:GM1WA55311A")
      (libsource (lib "eagle-import") (part "GM1WA55311A"))
    )
    (comp (ref "LED248")
      (value "GM1WA55311A")
      (footprint "eagle-import:GM1WA55311A")
      (libsource (lib "eagle-import") (part "GM1WA55311A"))
    )
    (comp (ref "LED249")
      (value "GM1WA55311A")
      (footprint "eagle-import:GM1WA55311A")
      (libsource (lib "eagle-import") (part "GM1WA55311A"))
    )
    (comp (ref "LED250")
      (value "GM1WA55311A")
      (footprint "eagle-import:GM1WA55311A")
      (libsource (lib "eagle-import") (part "GM1WA55311A"))
    )
    (comp (ref "LED251")
      (value "GM1WA55311A")
      (footprint "eagle-import:GM1WA55311A")
      (libsource (lib "eagle-import") (part "GM1WA55311A"))
    )
    (comp (ref "LED252")
      (value "GM1WA55311A")
      (footprint "eagle-import:GM1WA55311A")
      (libsource (lib "eagle-import") (part "GM1WA55311A"))
    )
    (comp (ref "LED253")
      (value "GM1WA55311A")
      (footprint "eagle-import:GM1WA55311A")
      (libsource (lib "eagle-import") (part "GM1WA55311A"))
    )
    (comp (ref "LED254")
      (value "GM1WA55311A")
      (footprint "eagle-import:GM1WA55311A")
      (libsource (lib "eagle-import") (part "GM1WA55311A"))
    )
    (comp (ref "LED255")
      (value "GM1WA55311A")
      (footprint "eagle-import:GM1WA55311A")
      (libsource (lib "eagle-import") (part "GM1WA55311A"))
    )
    (comp (ref "LED256")
      (value "GM1WA55311A")
      (footprint "eagle-import:GM1WA55311A")
      (libsource (lib "eagle-import") (part "GM1WA55311A"))
    )
  )
  (nets
    (net (code "1") (name "/B0") (class "Default")
      (node (ref "LED1") (pin "1") (pinfunction "CGREEN_1") (pintype "passive"))
      (node (ref "LED113") (pin "1") (pinfunction "CGREEN_1") (pintype "passive"))
      (node (ref "LED129") (pin "1") (pinfunction "CGREEN_1") (pintype "passive"))
      (node (ref "LED145") (pin "1") (pinfunction "CGREEN_1") (pintype "passive"))
      (node (ref "LED161") (pin "1") (pinfunction "CGREEN_1") (pintype "passive"))
      (node (ref "LED17") (pin "1") (pinfunction "CGREEN_1") (pintype "passive"))
      (node (ref "LED177") (pin "1") (pinfunction "CGREEN_1") (pintype "passive"))
      (node (ref "LED193") (pin "1") (pinfunction "CGREEN_1") (pintype "passive"))
      (node (ref "LED209") (pin "1") (pinfunction "CGREEN_1") (pintype "passive"))
      (node (ref "LED225") (pin "1") (pinfunction "CGREEN_1") (pintype "passive"))
      (node (ref "LED241") (pin "1") (pinfunction "CGREEN_1") (pintype "passive"))
      (node (ref "LED33") (pin "1") (pinfunction "CGREEN_1") (pintype "passive"))
      (node (ref "LED49") (pin "1") (pinfunction "CGREEN_1") (pintype "passive"))
      (node (ref "LED65") (pin "1") (pinfunction "CGREEN_1") (pintype "passive"))
      (node (ref "LED81") (pin "1") (pinfunction "CGREEN_1") (pintype "passive"))
      (node (ref "LED97") (pin "1") (pinfunction "CGREEN_1") (pintype "passive"))
    )
    (net (code "2") (name "/B1") (class "Default")
      (node (ref "LED114") (pin "1") (pinfunction "CGREEN_1") (pintype "passive"))
      (node (ref "LED130") (pin "1") (pinfunction "CGREEN_1") (pintype "passive"))
      (node (ref "LED146") (pin "1") (pinfunction "CGREEN_1") (pintype "passive"))
      (node (ref "LED162") (pin "1") (pinfunction "CGREEN_1") (pintype "passive"))
      (node (ref "LED178") (pin "1") (pinfunction "CGREEN_1") (pintype "passive"))
      (node (ref "LED18") (pin "1") (pinfunction "CGREEN_1") (pintype "passive"))
      (node (ref "LED194") (pin "1") (pinfunction "CGREEN_1") (pintype "passive"))
      (node (ref "LED2") (pin "1") (pinfunction "CGREEN_1") (pintype "passive"))
      (node (ref "LED210") (pin "1") (pinfunction "CGREEN_1") (pintype "passive"))
      (node (ref "LED226") (pin "1") (pinfunction "CGREEN_1") (pintype "passive"))
      (node (ref "LED242") (pin "1") (pinfunction "CGREEN_1") (pintype "passive"))
      (node (ref "LED34") (pin "1") (pinfunction "CGREEN_1") (pintype "passive"))
      (node (ref "LED50") (pin "1") (pinfunction "CGREEN_1") (pintype "passive"))
      (node (ref "LED66") (pin "1") (pinfunction "CGREEN_1") (pintype "passive"))
      (node (ref "LED82") (pin "1") (pinfunction "CGREEN_1") (pintype "passive"))
      (node (ref "LED98") (pin "1") (pinfunction "CGREEN_1") (pintype "passive"))
    )
    (net (code "3") (name "/B2") (class "Default")
      (node (ref "LED115") (pin "1") (pinfunction "CGREEN_1") (pintype "passive"))
      (node (ref "LED131") (pin "1") (pinfunction "CGREEN_1") (pintype "passive"))
      (node (ref "LED147") (pin "1") (pinfunction "CGREEN_1") (pintype "passive"))
      (node (ref "LED163") (pin "1") (pinfunction "CGREEN_1") (pintype "passive"))
      (node (ref "LED179") (pin "1") (pinfunction "CGREEN_1") (pintype "passive"))
      (node (ref "LED19") (pin "1") (pinfunction "CGREEN_1") (pintype "passive"))
      (node (ref "LED195") (pin "1") (pinfunction "CGREEN_1") (pintype "passive"))
      (node (ref "LED211") (pin "1") (pinfunction "CGREEN_1") (pintype "passive"))
      (node (ref "LED227") (pin "1") (pinfunction "CGREEN_1") (pintype "passive"))
      (node (ref "LED243") (pin "1") (pinfunction "CGREEN_1") (pintype "passive"))
      (node (ref "LED3") (pin "1") (pinfunction "CGREEN_1") (pintype "passive"))
      (node (ref "LED35") (pin "1") (pinfunction "CGREEN_1") (pintype "passive"))
      (node (ref "LED51") (pin "1") (pinfunction "CGREEN_1") (pintype "passive"))
      (node (ref "LED67") (pin "1") (pinfunction "CGREEN_1") (pintype "passive"))
      (node (ref "LED83") (pin "1") (pinfunction "CGREEN_1") (pintype "passive"))
      (node (ref "LED99") (pin "1") (pinfunction "CGREEN_1") (pintype "passive"))
    )
    (net (code "4") (name "/B3") (class "Default")
      (node (ref "LED100") (pin "1") (pinfunction "CGREEN_1") (pintype "passive"))
      (node (ref "LED116") (pin "1") (pinfunction "CGREEN_1") (pintype "passive"))
      (node (ref "LED132") (pin "1") (pinfunction "CGREEN_1") (pintype "passive"))
      (node (ref "LED148") (pin "1") (pinfunction "CGREEN_1") (pintype "passive"))
      (node (ref "LED164") (pin "1") (pinfunction "CGREEN_1") (pintype "passive"))
      (node (ref "LED180") (pin "1") (pinfunction "CGREEN_1") (pintype "passive"))
      (node (ref "LED196") (pin "1") (pinfunction "CGREEN_1") (pintype "passive"))
      (node (ref "LED20") (pin "1") (pinfunction "CGREEN_1") (pintype "passive"))
      (node (ref "LED212") (pin "1") (pinfunction "CGREEN_1") (pintype "passive"))
      (node (ref "LED228") (pin "1") (pinfunction "CGREEN_1") (pintype "passive"))
      (node (ref "LED244") (pin "1") (pinfunction "CGREEN_1") (pintype "passive"))
      (node (ref "LED36") (pin "1") (pinfunction "CGREEN_1") (pintype "passive"))
      (node (ref "LED4") (pin "1") (pinfunction "CGREEN_1") (pintype "passive"))
      (node (ref "LED52") (pin "1") (pinfunction "CGREEN_1") (pintype "passive"))
      (node (ref "LED68") (pin "1") (pinfunction "CGREEN_1") (pintype "passive"))
      (node (ref "LED84") (pin "1") (pinfunction "CGREEN_1") (pintype "passive"))
    )
    (net (code "5") (name "/B4") (class "Default")
      (node (ref "LED101") (pin "1") (pinfunction "CGREEN_1") (pintype "passive"))
      (node (ref "LED117") (pin "1") (pinfunction "CGREEN_1") (pintype "passive"))
      (node (ref "LED133") (pin "1") (pinfunction "CGREEN_1") (pintype "passive"))
      (node (ref "LED149") (pin "1") (pinfunction "CGREEN_1") (pintype "passive"))
      (node (ref "LED165") (pin "1") (pinfunction "CGREEN_1") (pintype "passive"))
      (node (ref "LED181") (pin "1") (pinfunction "CGREEN_1") (pintype "passive"))
      (node (ref "LED197") (pin "1") (pinfunction "CGREEN_1") (pintype "passive"))
      (node (ref "LED21") (pin "1") (pinfunction "CGREEN_1") (pintype "passive"))
      (node (ref "LED213") (pin "1") (pinfunction "CGREEN_1") (pintype "passive"))
      (node (ref "LED229") (pin "1") (pinfunction "CGREEN_1") (pintype "passive"))
      (node (ref "LED245") (pin "1") (pinfunction "CGREEN_1") (pintype "passive"))
      (node (ref "LED37") (pin "1") (pinfunction "CGREEN_1") (pintype "passive"))
      (node (ref "LED5") (pin "1") (pinfunction "CGREEN_1") (pintype "passive"))
      (node (ref "LED53") (pin "1") (pinfunction "CGREEN_1") (pintype "passive"))
      (node (ref "LED69") (pin "1") (pinfunction "CGREEN_1") (pintype "passive"))
      (node (ref "LED85") (pin "1") (pinfunction "CGREEN_1") (pintype "passive"))
    )
    (net (code "6") (name "/B5") (class "Default")
      (node (ref "LED102") (pin "1") (pinfunction "CGREEN_1") (pintype "passive"))
      (node (ref "LED118") (pin "1") (pinfunction "CGREEN_1") (pintype "passive"))
      (node (ref "LED134") (pin "1") (pinfunction "CGREEN_1") (pintype "passive"))
      (node (ref "LED150") (pin "1") (pinfunction "CGREEN_1") (pintype "passive"))
      (node (ref "LED166") (pin "1") (pinfunction "CGREEN_1") (pintype "passive"))
      (node (ref "LED182") (pin "1") (pinfunction "CGREEN_1") (pintype "passive"))
      (node (ref "LED198") (pin "1") (pinfunction "CGREEN_1") (pintype "passive"))
      (node (ref "LED214") (pin "1") (pinfunction "CGREEN_1") (pintype "passive"))
      (node (ref "LED22") (pin "1") (pinfunction "CGREEN_1") (pintype "passive"))
      (node (ref "LED230") (pin "1") (pinfunction "CGREEN_1") (pintype "passive"))
      (node (ref "LED246") (pin "1") (pinfunction "CGREEN_1") (pintype "passive"))
      (node (ref "LED38") (pin "1") (pinfunction "CGREEN_1") (pintype "passive"))
      (node (ref "LED54") (pin "1") (pinfunction "CGREEN_1") (pintype "passive"))
      (node (ref "LED6") (pin "1") (pinfunction "CGREEN_1") (pintype "passive"))
      (node (ref "LED70") (pin "1") (pinfunction "CGREEN_1") (pintype "passive"))
      (node (ref "LED86") (pin "1") (pinfunction "CGREEN_1") (pintype "passive"))
    )
    (net (code "7") (name "/B6") (class "Default")
      (node (ref "LED103") (pin "1") (pinfunction "CGREEN_1") (pintype "passive"))
      (node (ref "LED119") (pin "1") (pinfunction "CGREEN_1") (pintype "passive"))
      (node (ref "LED135") (pin "1") (pinfunction "CGREEN_1") (pintype "passive"))
      (node (ref "LED151") (pin "1") (pinfunction "CGREEN_1") (pintype "passive"))
      (node (ref "LED167") (pin "1") (pinfunction "CGREEN_1") (pintype "passive"))
      (node (ref "LED183") (pin "1") (pinfunction "CGREEN_1") (pintype "passive"))
      (node (ref "LED199") (pin "1") (pinfunction "CGREEN_1") (pintype "passive"))
      (node (ref "LED215") (pin "1") (pinfunction "CGREEN_1") (pintype "passive"))
      (node (ref "LED23") (pin "1") (pinfunction "CGREEN_1") (pintype "passive"))
      (node (ref "LED231") (pin "1") (pinfunction "CGREEN_1") (pintype "passive"))
      (node (ref "LED247") (pin "1") (pinfunction "CGREEN_1") (pintype "passive"))
      (node (ref "LED39") (pin "1") (pinfunction "CGREEN_1") (pintype "passive"))
      (node (ref "LED55") (pin "1") (pinfunction "CGREEN_1") (pintype "passive"))
      (node (ref "LED7") (pin "1") (pinfunction "CGREEN_1") (pintype "passive"))
      (node (ref "LED71") (pin "1") (pinfunction "CGREEN_1") (pintype "passive"))
      (node (ref "LED87") (pin "1") (pinfunction "CGREEN_1") (pintype "passive"))
    )
    (net (code "8") (name "/B7") (class "Default")
      (node (ref "LED104") (pin "1") (pinfunction "CGREEN_1") (pintype "passive"))
      (node (ref "LED120") (pin "1") (pinfunction "CGREEN_1") (pintype "passive"))
      (node (ref "LED136") (pin "1") (pinfunction "CGREEN_1") (pintype "passive"))
      (node (ref "LED152") (pin "1") (pinfunction "CGREEN_1") (pintype "passive"))
      (node (ref "LED168") (pin "1") (pinfunction "CGREEN_1") (pintype "passive"))
      (node (ref "LED184") (pin "1") (pinfunction "CGREEN_1") (pintype "passive"))
      (node (ref "LED200") (pin "1") (pinfunction "CGREEN_1") (pintype "passive"))
      (node (ref "LED216") (pin "1") (pinfunction "CGREEN_1") (pintype "passive"))
      (node (ref "LED232") (pin "1") (pinfunction "CGREEN_1") (pintype "passive"))
      (node (ref "LED24") (pin "1") (pinfunction "CGREEN_1") (pintype "passive"))
      (node (ref "LED248") (pin "1") (pinfunction "CGREEN_1") (pintype "passive"))
      (node (ref "LED40") (pin "1") (pinfunction "CGREEN_1") (pintype "passive"))
      (node (ref "LED56") (pin "1") (pinfunction "CGREEN_1") (pintype "passive"))
      (node (ref "LED72") (pin "1") (pinfunction "CGREEN_1") (pintype "passive"))
      (node (ref "LED8") (pin "1") (pinfunction "CGREEN_1") (pintype "passive"))
      (node (ref "LED88") (pin "1") (pinfunction "CGREEN_1") (pintype "passive"))
    )
    (net (code "9") (name "/B8") (class "Default")
      (node (ref "LED105") (pin "1") (pinfunction "CGREEN_1") (pintype "passive"))
      (node (ref "LED121") (pin "1") (pinfunction "CGREEN_1") (pintype "passive"))
      (node (ref "LED137") (pin "1") (pinfunction "CGREEN_1") (pintype "passive"))
      (node (ref "LED153") (pin "1") (pinfunction "CGREEN_1") (pintype "passive"))
      (node (ref "LED169") (pin "1") (pinfunction "CGREEN_1") (pintype "passive"))
      (node (ref "LED185") (pin "1") (pinfunction "CGREEN_1") (pintype "passive"))
      (node (ref "LED201") (pin "1") (pinfunction "CGREEN_1") (pintype "passive"))
      (node (ref "LED217") (pin "1") (pinfunction "CGREEN_1") (pintype "passive"))
      (node (ref "LED233") (pin "1") (pinfunction "CGREEN_1") (pintype "passive"))
      (node (ref "LED249") (pin "1") (pinfunction "CGREEN_1") (pintype "passive"))
      (node (ref "LED25") (pin "1") (pinfunction "CGREEN_1") (pintype "passive"))
      (node (ref "LED41") (pin "1") (pinfunction "CGREEN_1") (pintype "passive"))
      (node (ref "LED57") (pin "1") (pinfunction "CGREEN_1") (pintype "passive"))
      (node (ref "LED73") (pin "1") (pinfunction "CGREEN_1") (pintype "passive"))
      (node (ref "LED89") (pin "1") (pinfunction "CGREEN_1") (pintype "passive"))
      (node (ref "LED9") (pin "1") (pinfunction "CGREEN_1") (pintype "passive"))
    )
    (net (code "10") (name "/B9") (class "Default")
      (node (ref "LED10") (pin "1") (pinfunction "CGREEN_1") (pintype "passive"))
      (node (ref "LED106") (pin "1") (pinfunction "CGREEN_1") (pintype "passive"))
      (node (ref "LED122") (pin "1") (pinfunction "CGREEN_1") (pintype "passive"))
      (node (ref "LED138") (pin "1") (pinfunction "CGREEN_1") (pintype "passive"))
      (node (ref "LED154") (pin "1") (pinfunction "CGREEN_1") (pintype "passive"))
      (node (ref "LED170") (pin "1") (pinfunction "CGREEN_1") (pintype "passive"))
      (node (ref "LED186") (pin "1") (pinfunction "CGREEN_1") (pintype "passive"))
      (node (ref "LED202") (pin "1") (pinfunction "CGREEN_1") (pintype "passive"))
      (node (ref "LED218") (pin "1") (pinfunction "CGREEN_1") (pintype "passive"))
      (node (ref "LED234") (pin "1") (pinfunction "CGREEN_1") (pintype "passive"))
      (node (ref "LED250") (pin "1") (pinfunction "CGREEN_1") (pintype "passive"))
      (node (ref "LED26") (pin "1") (pinfunction "CGREEN_1") (pintype "passive"))
      (node (ref "LED42") (pin "1") (pinfunction "CGREEN_1") (pintype "passive"))
      (node (ref "LED58") (pin "1") (pinfunction "CGREEN_1") (pintype "passive"))
      (node (ref "LED74") (pin "1") (pinfunction "CGREEN_1") (pintype "passive"))
      (node (ref "LED90") (pin "1") (pinfunction "CGREEN_1") (pintype "passive"))
    )
    (net (code "11") (name "/B10") (class "Default")
      (node (ref "LED107") (pin "1") (pinfunction "CGREEN_1") (pintype "passive"))
      (node (ref "LED11") (pin "1") (pinfunction "CGREEN_1") (pintype "passive"))
      (node (ref "LED123") (pin "1") (pinfunction "CGREEN_1") (pintype "passive"))
      (node (ref "LED139") (pin "1") (pinfunction "CGREEN_1") (pintype "passive"))
      (node (ref "LED155") (pin "1") (pinfunction "CGREEN_1") (pintype "passive"))
      (node (ref "LED171") (pin "1") (pinfunction "CGREEN_1") (pintype "passive"))
      (node (ref "LED187") (pin "1") (pinfunction "CGREEN_1") (pintype "passive"))
      (node (ref "LED203") (pin "1") (pinfunction "CGREEN_1") (pintype "passive"))
      (node (ref "LED219") (pin "1") (pinfunction "CGREEN_1") (pintype "passive"))
      (node (ref "LED235") (pin "1") (pinfunction "CGREEN_1") (pintype "passive"))
      (node (ref "LED251") (pin "1") (pinfunction "CGREEN_1") (pintype "passive"))
      (node (ref "LED27") (pin "1") (pinfunction "CGREEN_1") (pintype "passive"))
      (node (ref "LED43") (pin "1") (pinfunction "CGREEN_1") (pintype "passive"))
      (node (ref "LED59") (pin "1") (pinfunction "CGREEN_1") (pintype "passive"))
      (node (ref "LED75") (pin "1") (pinfunction "CGREEN_1") (pintype "passive"))
      (node (ref "LED91") (pin "1") (pinfunction "CGREEN_1") (pintype "passive"))
    )
    (net (code "12") (name "/B11") (class "Default")
      (node (ref "LED108") (pin "1") (pinfunction "CGREEN_1") (pintype "passive"))
      (node (ref "LED12") (pin "1") (pinfunction "CGREEN_1") (pintype "passive"))
      (node (ref "LED124") (pin "1") (pinfunction "CGREEN_1") (pintype "passive"))
      (node (ref "LED140") (pin "1") (pinfunction "CGREEN_1") (pintype "passive"))
      (node (ref "LED156") (pin "1") (pinfunction "CGREEN_1") (pintype "passive"))
      (node (ref "LED172") (pin "1") (pinfunction "CGREEN_1") (pintype "passive"))
      (node (ref "LED188") (pin "1") (pinfunction "CGREEN_1") (pintype "passive"))
      (node (ref "LED204") (pin "1") (pinfunction "CGREEN_1") (pintype "passive"))
      (node (ref "LED220") (pin "1") (pinfunction "CGREEN_1") (pintype "passive"))
      (node (ref "LED236") (pin "1") (pinfunction "CGREEN_1") (pintype "passive"))
      (node (ref "LED252") (pin "1") (pinfunction "CGREEN_1") (pintype "passive"))
      (node (ref "LED28") (pin "1") (pinfunction "CGREEN_1") (pintype "passive"))
      (node (ref "LED44") (pin "1") (pinfunction "CGREEN_1") (pintype "passive"))
      (node (ref "LED60") (pin "1") (pinfunction "CGREEN_1") (pintype "passive"))
      (node (ref "LED76") (pin "1") (pinfunction "CGREEN_1") (pintype "passive"))
      (node (ref "LED92") (pin "1") (pinfunction "CGREEN_1") (pintype "passive"))
    )
    (net (code "13") (name "/B12") (class "Default")
      (node (ref "LED109") (pin "1") (pinfunction "CGREEN_1") (pintype "passive"))
      (node (ref "LED125") (pin "1") (pinfunction "CGREEN_1") (pintype "passive"))
      (node (ref "LED13") (pin "1") (pinfunction "CGREEN_1") (pintype "passive"))
      (node (ref "LED141") (pin "1") (pinfunction "CGREEN_1") (pintype "passive"))
      (node (ref "LED157") (pin "1") (pinfunction "CGREEN_1") (pintype "passive"))
      (node (ref "LED173") (pin "1") (pinfunction "CGREEN_1") (pintype "passive"))
      (node (ref "LED189") (pin "1") (pinfunction "CGREEN_1") (pintype "passive"))
      (node (ref "LED205") (pin "1") (pinfunction "CGREEN_1") (pintype "passive"))
      (node (ref "LED221") (pin "1") (pinfunction "CGREEN_1") (pintype "passive"))
      (node (ref "LED237") (pin "1") (pinfunction "CGREEN_1") (pintype "passive"))
      (node (ref "LED253") (pin "1") (pinfunction "CGREEN_1") (pintype "passive"))
      (node (ref "LED29") (pin "1") (pinfunction "CGREEN_1") (pintype "passive"))
      (node (ref "LED45") (pin "1") (pinfunction "CGREEN_1") (pintype "passive"))
      (node (ref "LED61") (pin "1") (pinfunction "CGREEN_1") (pintype "passive"))
      (node (ref "LED77") (pin "1") (pinfunction "CGREEN_1") (pintype "passive"))
      (node (ref "LED93") (pin "1") (pinfunction "CGREEN_1") (pintype "passive"))
    )
    (net (code "14") (name "/B13") (class "Default")
      (node (ref "LED110") (pin "1") (pinfunction "CGREEN_1") (pintype "passive"))
      (node (ref "LED126") (pin "1") (pinfunction "CGREEN_1") (pintype "passive"))
      (node (ref "LED14") (pin "1") (pinfunction "CGREEN_1") (pintype "passive"))
      (node (ref "LED142") (pin "1") (pinfunction "CGREEN_1") (pintype "passive"))
      (node (ref "LED158") (pin "1") (pinfunction "CGREEN_1") (pintype "passive"))
      (node (ref "LED174") (pin "1") (pinfunction "CGREEN_1") (pintype "passive"))
      (node (ref "LED190") (pin "1") (pinfunction "CGREEN_1") (pintype "passive"))
      (node (ref "LED206") (pin "1") (pinfunction "CGREEN_1") (pintype "passive"))
      (node (ref "LED222") (pin "1") (pinfunction "CGREEN_1") (pintype "passive"))
      (node (ref "LED238") (pin "1") (pinfunction "CGREEN_1") (pintype "passive"))
      (node (ref "LED254") (pin "1") (pinfunction "CGREEN_1") (pintype "passive"))
      (node (ref "LED30") (pin "1") (pinfunction "CGREEN_1") (pintype "passive"))
      (node (ref "LED46") (pin "1") (pinfunction "CGREEN_1") (pintype "passive"))
      (node (ref "LED62") (pin "1") (pinfunction "CGREEN_1") (pintype "passive"))
      (node (ref "LED78") (pin "1") (pinfunction "CGREEN_1") (pintype "passive"))
      (node (ref "LED94") (pin "1") (pinfunction "CGREEN_1") (pintype "passive"))
    )
    (net (code "15") (name "/B14") (class "Default")
      (node (ref "LED111") (pin "1") (pinfunction "CGREEN_1") (pintype "passive"))
      (node (ref "LED127") (pin "1") (pinfunction "CGREEN_1") (pintype "passive"))
      (node (ref "LED143") (pin "1") (pinfunction "CGREEN_1") (pintype "passive"))
      (node (ref "LED15") (pin "1") (pinfunction "CGREEN_1") (pintype "passive"))
      (node (ref "LED159") (pin "1") (pinfunction "CGREEN_1") (pintype "passive"))
      (node (ref "LED175") (pin "1") (pinfunction "CGREEN_1") (pintype "passive"))
      (node (ref "LED191") (pin "1") (pinfunction "CGREEN_1") (pintype "passive"))
      (node (ref "LED207") (pin "1") (pinfunction "CGREEN_1") (pintype "passive"))
      (node (ref "LED223") (pin "1") (pinfunction "CGREEN_1") (pintype "passive"))
      (node (ref "LED239") (pin "1") (pinfunction "CGREEN_1") (pintype "passive"))
      (node (ref "LED255") (pin "1") (pinfunction "CGREEN_1") (pintype "passive"))
      (node (ref "LED31") (pin "1") (pinfunction "CGREEN_1") (pintype "passive"))
      (node (ref "LED47") (pin "1") (pinfunction "CGREEN_1") (pintype "passive"))
      (node (ref "LED63") (pin "1") (pinfunction "CGREEN_1") (pintype "passive"))
      (node (ref "LED79") (pin "1") (pinfunction "CGREEN_1") (pintype "passive"))
      (node (ref "LED95") (pin "1") (pinfunction "CGREEN_1") (pintype "passive"))
    )
    (net (code "16") (name "/B15") (class "Default")
      (node (ref "LED112") (pin "1") (pinfunction "CGREEN_1") (pintype "passive"))
      (node (ref "LED128") (pin "1") (pinfunction "CGREEN_1") (pintype "passive"))
      (node (ref "LED144") (pin "1") (pinfunction "CGREEN_1") (pintype "passive"))
      (node (ref "LED16") (pin "1") (pinfunction "CGREEN_1") (pintype "passive"))
      (node (ref "LED160") (pin "1") (pinfunction "CGREEN_1") (pintype "passive"))
      (node (ref "LED176") (pin "1") (pinfunction "CGREEN_1") (pintype "passive"))
      (node (ref "LED192") (pin "1") (pinfunction "CGREEN_1") (pintype "passive"))
      (node (ref "LED208") (pin "1") (pinfunction "CGREEN_1") (pintype "passive"))
      (node (ref "LED224") (pin "1") (pinfunction "CGREEN_1") (pintype "passive"))
      (node (ref "LED240") (pin "1") (pinfunction "CGREEN_1") (pintype "passive"))
      (node (ref "LED256") (pin "1") (pinfunction "CGREEN_1") (pintype "passive"))
      (node (ref "LED32") (pin "1") (pinfunction "CGREEN_1") (pintype "passive"))
      (node (ref "LED48") (pin "1") (pinfunction "CGREEN_1") (pintype "passive"))
      (node (ref "LED64") (pin "1") (pinfunction "CGREEN_1") (pintype "passive"))
      (node (ref "LED80") (pin "1") (pinfunction "CGREEN_1") (pintype "passive"))
      (node (ref "LED96") (pin "1") (pinfunction "CGREEN_1") (pintype "passive"))
    )
    (net (code "17") (name "/G0") (class "Default")
      (node (ref "LED1") (pin "3") (pinfunction "CBLUE_3") (pintype "passive"))
      (node (ref "LED113") (pin "3") (pinfunction "CBLUE_3") (pintype "passive"))
      (node (ref "LED129") (pin "3") (pinfunction "CBLUE_3") (pintype "passive"))
      (node (ref "LED145") (pin "3") (pinfunction "CBLUE_3") (pintype "passive"))
      (node (ref "LED161") (pin "3") (pinfunction "CBLUE_3") (pintype "passive"))
      (node (ref "LED17") (pin "3") (pinfunction "CBLUE_3") (pintype "passive"))
      (node (ref "LED177") (pin "3") (pinfunction "CBLUE_3") (pintype "passive"))
      (node (ref "LED193") (pin "3") (pinfunction "CBLUE_3") (pintype "passive"))
      (node (ref "LED209") (pin "3") (pinfunction "CBLUE_3") (pintype "passive"))
      (node (ref "LED225") (pin "3") (pinfunction "CBLUE_3") (pintype "passive"))
      (node (ref "LED241") (pin "3") (pinfunction "CBLUE_3") (pintype "passive"))
      (node (ref "LED33") (pin "3") (pinfunction "CBLUE_3") (pintype "passive"))
      (node (ref "LED49") (pin "3") (pinfunction "CBLUE_3") (pintype "passive"))
      (node (ref "LED65") (pin "3") (pinfunction "CBLUE_3") (pintype "passive"))
      (node (ref "LED81") (pin "3") (pinfunction "CBLUE_3") (pintype "passive"))
      (node (ref "LED97") (pin "3") (pinfunction "CBLUE_3") (pintype "passive"))
    )
    (net (code "18") (name "/G1") (class "Default")
      (node (ref "LED114") (pin "3") (pinfunction "CBLUE_3") (pintype "passive"))
      (node (ref "LED130") (pin "3") (pinfunction "CBLUE_3") (pintype "passive"))
      (node (ref "LED146") (pin "3") (pinfunction "CBLUE_3") (pintype "passive"))
      (node (ref "LED162") (pin "3") (pinfunction "CBLUE_3") (pintype "passive"))
      (node (ref "LED178") (pin "3") (pinfunction "CBLUE_3") (pintype "passive"))
      (node (ref "LED18") (pin "3") (pinfunction "CBLUE_3") (pintype "passive"))
      (node (ref "LED194") (pin "3") (pinfunction "CBLUE_3") (pintype "passive"))
      (node (ref "LED2") (pin "3") (pinfunction "CBLUE_3") (pintype "passive"))
      (node (ref "LED210") (pin "3") (pinfunction "CBLUE_3") (pintype "passive"))
      (node (ref "LED226") (pin "3") (pinfunction "CBLUE_3") (pintype "passive"))
      (node (ref "LED242") (pin "3") (pinfunction "CBLUE_3") (pintype "passive"))
      (node (ref "LED34") (pin "3") (pinfunction "CBLUE_3") (pintype "passive"))
      (node (ref "LED50") (pin "3") (pinfunction "CBLUE_3") (pintype "passive"))
      (node (ref "LED66") (pin "3") (pinfunction "CBLUE_3") (pintype "passive"))
      (node (ref "LED82") (pin "3") (pinfunction "CBLUE_3") (pintype "passive"))
      (node (ref "LED98") (pin "3") (pinfunction "CBLUE_3") (pintype "passive"))
    )
    (net (code "19") (name "/G2") (class "Default")
      (node (ref "LED115") (pin "3") (pinfunction "CBLUE_3") (pintype "passive"))
      (node (ref "LED131") (pin "3") (pinfunction "CBLUE_3") (pintype "passive"))
      (node (ref "LED147") (pin "3") (pinfunction "CBLUE_3") (pintype "passive"))
      (node (ref "LED163") (pin "3") (pinfunction "CBLUE_3") (pintype "passive"))
      (node (ref "LED179") (pin "3") (pinfunction "CBLUE_3") (pintype "passive"))
      (node (ref "LED19") (pin "3") (pinfunction "CBLUE_3") (pintype "passive"))
      (node (ref "LED195") (pin "3") (pinfunction "CBLUE_3") (pintype "passive"))
      (node (ref "LED211") (pin "3") (pinfunction "CBLUE_3") (pintype "passive"))
      (node (ref "LED227") (pin "3") (pinfunction "CBLUE_3") (pintype "passive"))
      (node (ref "LED243") (pin "3") (pinfunction "CBLUE_3") (pintype "passive"))
      (node (ref "LED3") (pin "3") (pinfunction "CBLUE_3") (pintype "passive"))
      (node (ref "LED35") (pin "3") (pinfunction "CBLUE_3") (pintype "passive"))
      (node (ref "LED51") (pin "3") (pinfunction "CBLUE_3") (pintype "passive"))
      (node (ref "LED67") (pin "3") (pinfunction "CBLUE_3") (pintype "passive"))
      (node (ref "LED83") (pin "3") (pinfunction "CBLUE_3") (pintype "passive"))
      (node (ref "LED99") (pin "3") (pinfunction "CBLUE_3") (pintype "passive"))
    )
    (net (code "20") (name "/G3") (class "Default")
      (node (ref "LED100") (pin "3") (pinfunction "CBLUE_3") (pintype "passive"))
      (node (ref "LED116") (pin "3") (pinfunction "CBLUE_3") (pintype "passive"))
      (node (ref "LED132") (pin "3") (pinfunction "CBLUE_3") (pintype "passive"))
      (node (ref "LED148") (pin "3") (pinfunction "CBLUE_3") (pintype "passive"))
      (node (ref "LED164") (pin "3") (pinfunction "CBLUE_3") (pintype "passive"))
      (node (ref "LED180") (pin "3") (pinfunction "CBLUE_3") (pintype "passive"))
      (node (ref "LED196") (pin "3") (pinfunction "CBLUE_3") (pintype "passive"))
      (node (ref "LED20") (pin "3") (pinfunction "CBLUE_3") (pintype "passive"))
      (node (ref "LED212") (pin "3") (pinfunction "CBLUE_3") (pintype "passive"))
      (node (ref "LED228") (pin "3") (pinfunction "CBLUE_3") (pintype "passive"))
      (node (ref "LED244") (pin "3") (pinfunction "CBLUE_3") (pintype "passive"))
      (node (ref "LED36") (pin "3") (pinfunction "CBLUE_3") (pintype "passive"))
      (node (ref "LED4") (pin "3") (pinfunction "CBLUE_3") (pintype "passive"))
      (node (ref "LED52") (pin "3") (pinfunction "CBLUE_3") (pintype "passive"))
      (node (ref "LED68") (pin "3") (pinfunction "CBLUE_3") (pintype "passive"))
      (node (ref "LED84") (pin "3") (pinfunction "CBLUE_3") (pintype "passive"))
    )
    (net (code "21") (name "/G4") (class "Default")
      (node (ref "LED101") (pin "3") (pinfunction "CBLUE_3") (pintype "passive"))
      (node (ref "LED117") (pin "3") (pinfunction "CBLUE_3") (pintype "passive"))
      (node (ref "LED133") (pin "3") (pinfunction "CBLUE_3") (pintype "passive"))
      (node (ref "LED149") (pin "3") (pinfunction "CBLUE_3") (pintype "passive"))
      (node (ref "LED165") (pin "3") (pinfunction "CBLUE_3") (pintype "passive"))
      (node (ref "LED181") (pin "3") (pinfunction "CBLUE_3") (pintype "passive"))
      (node (ref "LED197") (pin "3") (pinfunction "CBLUE_3") (pintype "passive"))
      (node (ref "LED21") (pin "3") (pinfunction "CBLUE_3") (pintype "passive"))
      (node (ref "LED213") (pin "3") (pinfunction "CBLUE_3") (pintype "passive"))
      (node (ref "LED229") (pin "3") (pinfunction "CBLUE_3") (pintype "passive"))
      (node (ref "LED245") (pin "3") (pinfunction "CBLUE_3") (pintype "passive"))
      (node (ref "LED37") (pin "3") (pinfunction "CBLUE_3") (pintype "passive"))
      (node (ref "LED5") (pin "3") (pinfunction "CBLUE_3") (pintype "passive"))
      (node (ref "LED53") (pin "3") (pinfunction "CBLUE_3") (pintype "passive"))
      (node (ref "LED69") (pin "3") (pinfunction "CBLUE_3") (pintype "passive"))
      (node (ref "LED85") (pin "3") (pinfunction "CBLUE_3") (pintype "passive"))
    )
    (net (code "22") (name "/G5") (class "Default")
      (node (ref "LED102") (pin "3") (pinfunction "CBLUE_3") (pintype "passive"))
      (node (ref "LED118") (pin "3") (pinfunction "CBLUE_3") (pintype "passive"))
      (node (ref "LED134") (pin "3") (pinfunction "CBLUE_3") (pintype "passive"))
      (node (ref "LED150") (pin "3") (pinfunction "CBLUE_3") (pintype "passive"))
      (node (ref "LED166") (pin "3") (pinfunction "CBLUE_3") (pintype "passive"))
      (node (ref "LED182") (pin "3") (pinfunction "CBLUE_3") (pintype "passive"))
      (node (ref "LED198") (pin "3") (pinfunction "CBLUE_3") (pintype "passive"))
      (node (ref "LED214") (pin "3") (pinfunction "CBLUE_3") (pintype "passive"))
      (node (ref "LED22") (pin "3") (pinfunction "CBLUE_3") (pintype "passive"))
      (node (ref "LED230") (pin "3") (pinfunction "CBLUE_3") (pintype "passive"))
      (node (ref "LED246") (pin "3") (pinfunction "CBLUE_3") (pintype "passive"))
      (node (ref "LED38") (pin "3") (pinfunction "CBLUE_3") (pintype "passive"))
      (node (ref "LED54") (pin "3") (pinfunction "CBLUE_3") (pintype "passive"))
      (node (ref "LED6") (pin "3") (pinfunction "CBLUE_3") (pintype "passive"))
      (node (ref "LED70") (pin "3") (pinfunction "CBLUE_3") (pintype "passive"))
      (node (ref "LED86") (pin "3") (pinfunction "CBLUE_3") (pintype "passive"))
    )
    (net (code "23") (name "/G6") (class "Default")
      (node (ref "LED103") (pin "3") (pinfunction "CBLUE_3") (pintype "passive"))
      (node (ref "LED119") (pin "3") (pinfunction "CBLUE_3") (pintype "passive"))
      (node (ref "LED135") (pin "3") (pinfunction "CBLUE_3") (pintype "passive"))
      (node (ref "LED151") (pin "3") (pinfunction "CBLUE_3") (pintype "passive"))
      (node (ref "LED167") (pin "3") (pinfunction "CBLUE_3") (pintype "passive"))
      (node (ref "LED183") (pin "3") (pinfunction "CBLUE_3") (pintype "passive"))
      (node (ref "LED199") (pin "3") (pinfunction "CBLUE_3") (pintype "passive"))
      (node (ref "LED215") (pin "3") (pinfunction "CBLUE_3") (pintype "passive"))
      (node (ref "LED23") (pin "3") (pinfunction "CBLUE_3") (pintype "passive"))
      (node (ref "LED231") (pin "3") (pinfunction "CBLUE_3") (pintype "passive"))
      (node (ref "LED247") (pin "3") (pinfunction "CBLUE_3") (pintype "passive"))
      (node (ref "LED39") (pin "3") (pinfunction "CBLUE_3") (pintype "passive"))
      (node (ref "LED55") (pin "3") (pinfunction "CBLUE_3") (pintype "passive"))
      (node (ref "LED7") (pin "3") (pinfunction "CBLUE_3") (pintype "passive"))
      (node (ref "LED71") (pin "3") (pinfunction "CBLUE_3") (pintype "passive"))
      (node (ref "LED87") (pin "3") (pinfunction "CBLUE_3") (pintype "passive"))
    )
    (net (code "24") (name "/G7") (class "Default")
      (node (ref "LED104") (pin "3") (pinfunction "CBLUE_3") (pintype "passive"))
      (node (ref "LED120") (pin "3") (pinfunction "CBLUE_3") (pintype "passive"))
      (node (ref "LED136") (pin "3") (pinfunction "CBLUE_3") (pintype "passive"))
      (node (ref "LED152") (pin "3") (pinfunction "CBLUE_3") (pintype "passive"))
      (node (ref "LED168") (pin "3") (pinfunction "CBLUE_3") (pintype "passive"))
      (node (ref "LED184") (pin "3") (pinfunction "CBLUE_3") (pintype "passive"))
      (node (ref "LED200") (pin "3") (pinfunction "CBLUE_3") (pintype "passive"))
      (node (ref "LED216") (pin "3") (pinfunction "CBLUE_3") (pintype "passive"))
      (node (ref "LED232") (pin "3") (pinfunction "CBLUE_3") (pintype "passive"))
      (node (ref "LED24") (pin "3") (pinfunction "CBLUE_3") (pintype "passive"))
      (node (ref "LED248") (pin "3") (pinfunction "CBLUE_3") (pintype "passive"))
      (node (ref "LED40") (pin "3") (pinfunction "CBLUE_3") (pintype "passive"))
      (node (ref "LED56") (pin "3") (pinfunction "CBLUE_3") (pintype "passive"))
      (node (ref "LED72") (pin "3") (pinfunction "CBLUE_3") (pintype "passive"))
      (node (ref "LED8") (pin "3") (pinfunction "CBLUE_3") (pintype "passive"))
      (node (ref "LED88") (pin "3") (pinfunction "CBLUE_3") (pintype "passive"))
    )
    (net (code "25") (name "/G8") (class "Default")
      (node (ref "LED105") (pin "3") (pinfunction "CBLUE_3") (pintype "passive"))
      (node (ref "LED121") (pin "3") (pinfunction "CBLUE_3") (pintype "passive"))
      (node (ref "LED137") (pin "3") (pinfunction "CBLUE_3") (pintype "passive"))
      (node (ref "LED153") (pin "3") (pinfunction "CBLUE_3") (pintype "passive"))
      (node (ref "LED169") (pin "3") (pinfunction "CBLUE_3") (pintype "passive"))
      (node (ref "LED185") (pin "3") (pinfunction "CBLUE_3") (pintype "passive"))
      (node (ref "LED201") (pin "3") (pinfunction "CBLUE_3") (pintype "passive"))
      (node (ref "LED217") (pin "3") (pinfunction "CBLUE_3") (pintype "passive"))
      (node (ref "LED233") (pin "3") (pinfunction "CBLUE_3") (pintype "passive"))
      (node (ref "LED249") (pin "3") (pinfunction "CBLUE_3") (pintype "passive"))
      (node (ref "LED25") (pin "3") (pinfunction "CBLUE_3") (pintype "passive"))
      (node (ref "LED41") (pin "3") (pinfunction "CBLUE_3") (pintype "passive"))
      (node (ref "LED57") (pin "3") (pinfunction "CBLUE_3") (pintype "passive"))
      (node (ref "LED73") (pin "3") (pinfunction "CBLUE_3") (pintype "passive"))
      (node (ref "LED89") (pin "3") (pinfunction "CBLUE_3") (pintype "passive"))
      (node (ref "LED9") (pin "3") (pinfunction "CBLUE_3") (pintype "passive"))
    )
    (net (code "26") (name "/G9") (class "Default")
      (node (ref "LED10") (pin "3") (pinfunction "CBLUE_3") (pintype "passive"))
      (node (ref "LED106") (pin "3") (pinfunction "CBLUE_3") (pintype "passive"))
      (node (ref "LED122") (pin "3") (pinfunction "CBLUE_3") (pintype "passive"))
      (node (ref "LED138") (pin "3") (pinfunction "CBLUE_3") (pintype "passive"))
      (node (ref "LED154") (pin "3") (pinfunction "CBLUE_3") (pintype "passive"))
      (node (ref "LED170") (pin "3") (pinfunction "CBLUE_3") (pintype "passive"))
      (node (ref "LED186") (pin "3") (pinfunction "CBLUE_3") (pintype "passive"))
      (node (ref "LED202") (pin "3") (pinfunction "CBLUE_3") (pintype "passive"))
      (node (ref "LED218") (pin "3") (pinfunction "CBLUE_3") (pintype "passive"))
      (node (ref "LED234") (pin "3") (pinfunction "CBLUE_3") (pintype "passive"))
      (node (ref "LED250") (pin "3") (pinfunction "CBLUE_3") (pintype "passive"))
      (node (ref "LED26") (pin "3") (pinfunction "CBLUE_3") (pintype "passive"))
      (node (ref "LED42") (pin "3") (pinfunction "CBLUE_3") (pintype "passive"))
      (node (ref "LED58") (pin "3") (pinfunction "CBLUE_3") (pintype "passive"))
      (node (ref "LED74") (pin "3") (pinfunction "CBLUE_3") (pintype "passive"))
      (node (ref "LED90") (pin "3") (pinfunction "CBLUE_3") (pintype "passive"))
    )
    (net (code "27") (name "/G10") (class "Default")
      (node (ref "LED107") (pin "3") (pinfunction "CBLUE_3") (pintype "passive"))
      (node (ref "LED11") (pin "3") (pinfunction "CBLUE_3") (pintype "passive"))
      (node (ref "LED123") (pin "3") (pinfunction "CBLUE_3") (pintype "passive"))
      (node (ref "LED139") (pin "3") (pinfunction "CBLUE_3") (pintype "passive"))
      (node (ref "LED155") (pin "3") (pinfunction "CBLUE_3") (pintype "passive"))
      (node (ref "LED171") (pin "3") (pinfunction "CBLUE_3") (pintype "passive"))
      (node (ref "LED187") (pin "3") (pinfunction "CBLUE_3") (pintype "passive"))
      (node (ref "LED203") (pin "3") (pinfunction "CBLUE_3") (pintype "passive"))
      (node (ref "LED219") (pin "3") (pinfunction "CBLUE_3") (pintype "passive"))
      (node (ref "LED235") (pin "3") (pinfunction "CBLUE_3") (pintype "passive"))
      (node (ref "LED251") (pin "3") (pinfunction "CBLUE_3") (pintype "passive"))
      (node (ref "LED27") (pin "3") (pinfunction "CBLUE_3") (pintype "passive"))
      (node (ref "LED43") (pin "3") (pinfunction "CBLUE_3") (pintype "passive"))
      (node (ref "LED59") (pin "3") (pinfunction "CBLUE_3") (pintype "passive"))
      (node (ref "LED75") (pin "3") (pinfunction "CBLUE_3") (pintype "passive"))
      (node (ref "LED91") (pin "3") (pinfunction "CBLUE_3") (pintype "passive"))
    )
    (net (code "28") (name "/G11") (class "Default")
      (node (ref "LED108") (pin "3") (pinfunction "CBLUE_3") (pintype "passive"))
      (node (ref "LED12") (pin "3") (pinfunction "CBLUE_3") (pintype "passive"))
      (node (ref "LED124") (pin "3") (pinfunction "CBLUE_3") (pintype "passive"))
      (node (ref "LED140") (pin "3") (pinfunction "CBLUE_3") (pintype "passive"))
      (node (ref "LED156") (pin "3") (pinfunction "CBLUE_3") (pintype "passive"))
      (node (ref "LED172") (pin "3") (pinfunction "CBLUE_3") (pintype "passive"))
      (node (ref "LED188") (pin "3") (pinfunction "CBLUE_3") (pintype "passive"))
      (node (ref "LED204") (pin "3") (pinfunction "CBLUE_3") (pintype "passive"))
      (node (ref "LED220") (pin "3") (pinfunction "CBLUE_3") (pintype "passive"))
      (node (ref "LED236") (pin "3") (pinfunction "CBLUE_3") (pintype "passive"))
      (node (ref "LED252") (pin "3") (pinfunction "CBLUE_3") (pintype "passive"))
      (node (ref "LED28") (pin "3") (pinfunction "CBLUE_3") (pintype "passive"))
      (node (ref "LED44") (pin "3") (pinfunction "CBLUE_3") (pintype "passive"))
      (node (ref "LED60") (pin "3") (pinfunction "CBLUE_3") (pintype "passive"))
      (node (ref "LED76") (pin "3") (pinfunction "CBLUE_3") (pintype "passive"))
      (node (ref "LED92") (pin "3") (pinfunction "CBLUE_3") (pintype "passive"))
    )
    (net (code "29") (name "/G12") (class "Default")
      (node (ref "LED109") (pin "3") (pinfunction "CBLUE_3") (pintype "passive"))
      (node (ref "LED125") (pin "3") (pinfunction "CBLUE_3") (pintype "passive"))
      (node (ref "LED13") (pin "3") (pinfunction "CBLUE_3") (pintype "passive"))
      (node (ref "LED141") (pin "3") (pinfunction "CBLUE_3") (pintype "passive"))
      (node (ref "LED157") (pin "3") (pinfunction "CBLUE_3") (pintype "passive"))
      (node (ref "LED173") (pin "3") (pinfunction "CBLUE_3") (pintype "passive"))
      (node (ref "LED189") (pin "3") (pinfunction "CBLUE_3") (pintype "passive"))
      (node (ref "LED205") (pin "3") (pinfunction "CBLUE_3") (pintype "passive"))
      (node (ref "LED221") (pin "3") (pinfunction "CBLUE_3") (pintype "passive"))
      (node (ref "LED237") (pin "3") (pinfunction "CBLUE_3") (pintype "passive"))
      (node (ref "LED253") (pin "3") (pinfunction "CBLUE_3") (pintype "passive"))
      (node (ref "LED29") (pin "3") (pinfunction "CBLUE_3") (pintype "passive"))
      (node (ref "LED45") (pin "3") (pinfunction "CBLUE_3") (pintype "passive"))
      (node (ref "LED61") (pin "3") (pinfunction "CBLUE_3") (pintype "passive"))
      (node (ref "LED77") (pin "3") (pinfunction "CBLUE_3") (pintype "passive"))
      (node (ref "LED93") (pin "3") (pinfunction "CBLUE_3") (pintype "passive"))
    )
    (net (code "30") (name "/G13") (class "Default")
      (node (ref "LED110") (pin "3") (pinfunction "CBLUE_3") (pintype "passive"))
      (node (ref "LED126") (pin "3") (pinfunction "CBLUE_3") (pintype "passive"))
      (node (ref "LED14") (pin "3") (pinfunction "CBLUE_3") (pintype "passive"))
      (node (ref "LED142") (pin "3") (pinfunction "CBLUE_3") (pintype "passive"))
      (node (ref "LED158") (pin "3") (pinfunction "CBLUE_3") (pintype "passive"))
      (node (ref "LED174") (pin "3") (pinfunction "CBLUE_3") (pintype "passive"))
      (node (ref "LED190") (pin "3") (pinfunction "CBLUE_3") (pintype "passive"))
      (node (ref "LED206") (pin "3") (pinfunction "CBLUE_3") (pintype "passive"))
      (node (ref "LED222") (pin "3") (pinfunction "CBLUE_3") (pintype "passive"))
      (node (ref "LED238") (pin "3") (pinfunction "CBLUE_3") (pintype "passive"))
      (node (ref "LED254") (pin "3") (pinfunction "CBLUE_3") (pintype "passive"))
      (node (ref "LED30") (pin "3") (pinfunction "CBLUE_3") (pintype "passive"))
      (node (ref "LED46") (pin "3") (pinfunction "CBLUE_3") (pintype "passive"))
      (node (ref "LED62") (pin "3") (pinfunction "CBLUE_3") (pintype "passive"))
      (node (ref "LED78") (pin "3") (pinfunction "CBLUE_3") (pintype "passive"))
      (node (ref "LED94") (pin "3") (pinfunction "CBLUE_3") (pintype "passive"))
    )
    (net (code "31") (name "/G14") (class "Default")
      (node (ref "LED111") (pin "3") (pinfunction "CBLUE_3") (pintype "passive"))
      (node (ref "LED127") (pin "3") (pinfunction "CBLUE_3") (pintype "passive"))
      (node (ref "LED143") (pin "3") (pinfunction "CBLUE_3") (pintype "passive"))
      (node (ref "LED15") (pin "3") (pinfunction "CBLUE_3") (pintype "passive"))
      (node (ref "LED159") (pin "3") (pinfunction "CBLUE_3") (pintype "passive"))
      (node (ref "LED175") (pin "3") (pinfunction "CBLUE_3") (pintype "passive"))
      (node (ref "LED191") (pin "3") (pinfunction "CBLUE_3") (pintype "passive"))
      (node (ref "LED207") (pin "3") (pinfunction "CBLUE_3") (pintype "passive"))
      (node (ref "LED223") (pin "3") (pinfunction "CBLUE_3") (pintype "passive"))
      (node (ref "LED239") (pin "3") (pinfunction "CBLUE_3") (pintype "passive"))
      (node (ref "LED255") (pin "3") (pinfunction "CBLUE_3") (pintype "passive"))
      (node (ref "LED31") (pin "3") (pinfunction "CBLUE_3") (pintype "passive"))
      (node (ref "LED47") (pin "3") (pinfunction "CBLUE_3") (pintype "passive"))
      (node (ref "LED63") (pin "3") (pinfunction "CBLUE_3") (pintype "passive"))
      (node (ref "LED79") (pin "3") (pinfunction "CBLUE_3") (pintype "passive"))
      (node (ref "LED95") (pin "3") (pinfunction "CBLUE_3") (pintype "passive"))
    )
    (net (code "32") (name "/G15") (class "Default")
      (node (ref "LED112") (pin "3") (pinfunction "CBLUE_3") (pintype "passive"))
      (node (ref "LED128") (pin "3") (pinfunction "CBLUE_3") (pintype "passive"))
      (node (ref "LED144") (pin "3") (pinfunction "CBLUE_3") (pintype "passive"))
      (node (ref "LED16") (pin "3") (pinfunction "CBLUE_3") (pintype "passive"))
      (node (ref "LED160") (pin "3") (pinfunction "CBLUE_3") (pintype "passive"))
      (node (ref "LED176") (pin "3") (pinfunction "CBLUE_3") (pintype "passive"))
      (node (ref "LED192") (pin "3") (pinfunction "CBLUE_3") (pintype "passive"))
      (node (ref "LED208") (pin "3") (pinfunction "CBLUE_3") (pintype "passive"))
      (node (ref "LED224") (pin "3") (pinfunction "CBLUE_3") (pintype "passive"))
      (node (ref "LED240") (pin "3") (pinfunction "CBLUE_3") (pintype "passive"))
      (node (ref "LED256") (pin "3") (pinfunction "CBLUE_3") (pintype "passive"))
      (node (ref "LED32") (pin "3") (pinfunction "CBLUE_3") (pintype "passive"))
      (node (ref "LED48") (pin "3") (pinfunction "CBLUE_3") (pintype "passive"))
      (node (ref "LED64") (pin "3") (pinfunction "CBLUE_3") (pintype "passive"))
      (node (ref "LED80") (pin "3") (pinfunction "CBLUE_3") (pintype "passive"))
      (node (ref "LED96") (pin "3") (pinfunction "CBLUE_3") (pintype "passive"))
    )
    (net (code "33") (name "/R0") (class "Default")
      (node (ref "LED1") (pin "2") (pinfunction "CRED_2") (pintype "passive"))
      (node (ref "LED113") (pin "2") (pinfunction "CRED_2") (pintype "passive"))
      (node (ref "LED129") (pin "2") (pinfunction "CRED_2") (pintype "passive"))
      (node (ref "LED145") (pin "2") (pinfunction "CRED_2") (pintype "passive"))
      (node (ref "LED161") (pin "2") (pinfunction "CRED_2") (pintype "passive"))
      (node (ref "LED17") (pin "2") (pinfunction "CRED_2") (pintype "passive"))
      (node (ref "LED177") (pin "2") (pinfunction "CRED_2") (pintype "passive"))
      (node (ref "LED193") (pin "2") (pinfunction "CRED_2") (pintype "passive"))
      (node (ref "LED209") (pin "2") (pinfunction "CRED_2") (pintype "passive"))
      (node (ref "LED225") (pin "2") (pinfunction "CRED_2") (pintype "passive"))
      (node (ref "LED241") (pin "2") (pinfunction "CRED_2") (pintype "passive"))
      (node (ref "LED33") (pin "2") (pinfunction "CRED_2") (pintype "passive"))
      (node (ref "LED49") (pin "2") (pinfunction "CRED_2") (pintype "passive"))
      (node (ref "LED65") (pin "2") (pinfunction "CRED_2") (pintype "passive"))
      (node (ref "LED81") (pin "2") (pinfunction "CRED_2") (pintype "passive"))
      (node (ref "LED97") (pin "2") (pinfunction "CRED_2") (pintype "passive"))
    )
    (net (code "34") (name "/R1") (class "Default")
      (node (ref "LED114") (pin "2") (pinfunction "CRED_2") (pintype "passive"))
      (node (ref "LED130") (pin "2") (pinfunction "CRED_2") (pintype "passive"))
      (node (ref "LED146") (pin "2") (pinfunction "CRED_2") (pintype "passive"))
      (node (ref "LED162") (pin "2") (pinfunction "CRED_2") (pintype "passive"))
      (node (ref "LED178") (pin "2") (pinfunction "CRED_2") (pintype "passive"))
      (node (ref "LED18") (pin "2") (pinfunction "CRED_2") (pintype "passive"))
      (node (ref "LED194") (pin "2") (pinfunction "CRED_2") (pintype "passive"))
      (node (ref "LED2") (pin "2") (pinfunction "CRED_2") (pintype "passive"))
      (node (ref "LED210") (pin "2") (pinfunction "CRED_2") (pintype "passive"))
      (node (ref "LED226") (pin "2") (pinfunction "CRED_2") (pintype "passive"))
      (node (ref "LED242") (pin "2") (pinfunction "CRED_2") (pintype "passive"))
      (node (ref "LED34") (pin "2") (pinfunction "CRED_2") (pintype "passive"))
      (node (ref "LED50") (pin "2") (pinfunction "CRED_2") (pintype "passive"))
      (node (ref "LED66") (pin "2") (pinfunction "CRED_2") (pintype "passive"))
      (node (ref "LED82") (pin "2") (pinfunction "CRED_2") (pintype "passive"))
      (node (ref "LED98") (pin "2") (pinfunction "CRED_2") (pintype "passive"))
    )
    (net (code "35") (name "/R2") (class "Default")
      (node (ref "LED115") (pin "2") (pinfunction "CRED_2") (pintype "passive"))
      (node (ref "LED131") (pin "2") (pinfunction "CRED_2") (pintype "passive"))
      (node (ref "LED147") (pin "2") (pinfunction "CRED_2") (pintype "passive"))
      (node (ref "LED163") (pin "2") (pinfunction "CRED_2") (pintype "passive"))
      (node (ref "LED179") (pin "2") (pinfunction "CRED_2") (pintype "passive"))
      (node (ref "LED19") (pin "2") (pinfunction "CRED_2") (pintype "passive"))
      (node (ref "LED195") (pin "2") (pinfunction "CRED_2") (pintype "passive"))
      (node (ref "LED211") (pin "2") (pinfunction "CRED_2") (pintype "passive"))
      (node (ref "LED227") (pin "2") (pinfunction "CRED_2") (pintype "passive"))
      (node (ref "LED243") (pin "2") (pinfunction "CRED_2") (pintype "passive"))
      (node (ref "LED3") (pin "2") (pinfunction "CRED_2") (pintype "passive"))
      (node (ref "LED35") (pin "2") (pinfunction "CRED_2") (pintype "passive"))
      (node (ref "LED51") (pin "2") (pinfunction "CRED_2") (pintype "passive"))
      (node (ref "LED67") (pin "2") (pinfunction "CRED_2") (pintype "passive"))
      (node (ref "LED83") (pin "2") (pinfunction "CRED_2") (pintype "passive"))
      (node (ref "LED99") (pin "2") (pinfunction "CRED_2") (pintype "passive"))
    )
    (net (code "36") (name "/R3") (class "Default")
      (node (ref "LED100") (pin "2") (pinfunction "CRED_2") (pintype "passive"))
      (node (ref "LED116") (pin "2") (pinfunction "CRED_2") (pintype "passive"))
      (node (ref "LED132") (pin "2") (pinfunction "CRED_2") (pintype "passive"))
      (node (ref "LED148") (pin "2") (pinfunction "CRED_2") (pintype "passive"))
      (node (ref "LED164") (pin "2") (pinfunction "CRED_2") (pintype "passive"))
      (node (ref "LED180") (pin "2") (pinfunction "CRED_2") (pintype "passive"))
      (node (ref "LED196") (pin "2") (pinfunction "CRED_2") (pintype "passive"))
      (node (ref "LED20") (pin "2") (pinfunction "CRED_2") (pintype "passive"))
      (node (ref "LED212") (pin "2") (pinfunction "CRED_2") (pintype "passive"))
      (node (ref "LED228") (pin "2") (pinfunction "CRED_2") (pintype "passive"))
      (node (ref "LED244") (pin "2") (pinfunction "CRED_2") (pintype "passive"))
      (node (ref "LED36") (pin "2") (pinfunction "CRED_2") (pintype "passive"))
      (node (ref "LED4") (pin "2") (pinfunction "CRED_2") (pintype "passive"))
      (node (ref "LED52") (pin "2") (pinfunction "CRED_2") (pintype "passive"))
      (node (ref "LED68") (pin "2") (pinfunction "CRED_2") (pintype "passive"))
      (node (ref "LED84") (pin "2") (pinfunction "CRED_2") (pintype "passive"))
    )
    (net (code "37") (name "/R4") (class "Default")
      (node (ref "LED101") (pin "2") (pinfunction "CRED_2") (pintype "passive"))
      (node (ref "LED117") (pin "2") (pinfunction "CRED_2") (pintype "passive"))
      (node (ref "LED133") (pin "2") (pinfunction "CRED_2") (pintype "passive"))
      (node (ref "LED149") (pin "2") (pinfunction "CRED_2") (pintype "passive"))
      (node (ref "LED165") (pin "2") (pinfunction "CRED_2") (pintype "passive"))
      (node (ref "LED181") (pin "2") (pinfunction "CRED_2") (pintype "passive"))
      (node (ref "LED197") (pin "2") (pinfunction "CRED_2") (pintype "passive"))
      (node (ref "LED21") (pin "2") (pinfunction "CRED_2") (pintype "passive"))
      (node (ref "LED213") (pin "2") (pinfunction "CRED_2") (pintype "passive"))
      (node (ref "LED229") (pin "2") (pinfunction "CRED_2") (pintype "passive"))
      (node (ref "LED245") (pin "2") (pinfunction "CRED_2") (pintype "passive"))
      (node (ref "LED37") (pin "2") (pinfunction "CRED_2") (pintype "passive"))
      (node (ref "LED5") (pin "2") (pinfunction "CRED_2") (pintype "passive"))
      (node (ref "LED53") (pin "2") (pinfunction "CRED_2") (pintype "passive"))
      (node (ref "LED69") (pin "2") (pinfunction "CRED_2") (pintype "passive"))
      (node (ref "LED85") (pin "2") (pinfunction "CRED_2") (pintype "passive"))
    )
    (net (code "38") (name "/R5") (class "Default")
      (node (ref "LED102") (pin "2") (pinfunction "CRED_2") (pintype "passive"))
      (node (ref "LED118") (pin "2") (pinfunction "CRED_2") (pintype "passive"))
      (node (ref "LED134") (pin "2") (pinfunction "CRED_2") (pintype "passive"))
      (node (ref "LED150") (pin "2") (pinfunction "CRED_2") (pintype "passive"))
      (node (ref "LED166") (pin "2") (pinfunction "CRED_2") (pintype "passive"))
      (node (ref "LED182") (pin "2") (pinfunction "CRED_2") (pintype "passive"))
      (node (ref "LED198") (pin "2") (pinfunction "CRED_2") (pintype "passive"))
      (node (ref "LED214") (pin "2") (pinfunction "CRED_2") (pintype "passive"))
      (node (ref "LED22") (pin "2") (pinfunction "CRED_2") (pintype "passive"))
      (node (ref "LED230") (pin "2") (pinfunction "CRED_2") (pintype "passive"))
      (node (ref "LED246") (pin "2") (pinfunction "CRED_2") (pintype "passive"))
      (node (ref "LED38") (pin "2") (pinfunction "CRED_2") (pintype "passive"))
      (node (ref "LED54") (pin "2") (pinfunction "CRED_2") (pintype "passive"))
      (node (ref "LED6") (pin "2") (pinfunction "CRED_2") (pintype "passive"))
      (node (ref "LED70") (pin "2") (pinfunction "CRED_2") (pintype "passive"))
      (node (ref "LED86") (pin "2") (pinfunction "CRED_2") (pintype "passive"))
    )
    (net (code "39") (name "/R6") (class "Default")
      (node (ref "LED103") (pin "2") (pinfunction "CRED_2") (pintype "passive"))
      (node (ref "LED119") (pin "2") (pinfunction "CRED_2") (pintype "passive"))
      (node (ref "LED135") (pin "2") (pinfunction "CRED_2") (pintype "passive"))
      (node (ref "LED151") (pin "2") (pinfunction "CRED_2") (pintype "passive"))
      (node (ref "LED167") (pin "2") (pinfunction "CRED_2") (pintype "passive"))
      (node (ref "LED183") (pin "2") (pinfunction "CRED_2") (pintype "passive"))
      (node (ref "LED199") (pin "2") (pinfunction "CRED_2") (pintype "passive"))
      (node (ref "LED215") (pin "2") (pinfunction "CRED_2") (pintype "passive"))
      (node (ref "LED23") (pin "2") (pinfunction "CRED_2") (pintype "passive"))
      (node (ref "LED231") (pin "2") (pinfunction "CRED_2") (pintype "passive"))
      (node (ref "LED247") (pin "2") (pinfunction "CRED_2") (pintype "passive"))
      (node (ref "LED39") (pin "2") (pinfunction "CRED_2") (pintype "passive"))
      (node (ref "LED55") (pin "2") (pinfunction "CRED_2") (pintype "passive"))
      (node (ref "LED7") (pin "2") (pinfunction "CRED_2") (pintype "passive"))
      (node (ref "LED71") (pin "2") (pinfunction "CRED_2") (pintype "passive"))
      (node (ref "LED87") (pin "2") (pinfunction "CRED_2") (pintype "passive"))
    )
    (net (code "40") (name "/R7") (class "Default")
      (node (ref "LED104") (pin "2") (pinfunction "CRED_2") (pintype "passive"))
      (node (ref "LED120") (pin "2") (pinfunction "CRED_2") (pintype "passive"))
      (node (ref "LED136") (pin "2") (pinfunction "CRED_2") (pintype "passive"))
      (node (ref "LED152") (pin "2") (pinfunction "CRED_2") (pintype "passive"))
      (node (ref "LED168") (pin "2") (pinfunction "CRED_2") (pintype "passive"))
      (node (ref "LED184") (pin "2") (pinfunction "CRED_2") (pintype "passive"))
      (node (ref "LED200") (pin "2") (pinfunction "CRED_2") (pintype "passive"))
      (node (ref "LED216") (pin "2") (pinfunction "CRED_2") (pintype "passive"))
      (node (ref "LED232") (pin "2") (pinfunction "CRED_2") (pintype "passive"))
      (node (ref "LED24") (pin "2") (pinfunction "CRED_2") (pintype "passive"))
      (node (ref "LED248") (pin "2") (pinfunction "CRED_2") (pintype "passive"))
      (node (ref "LED40") (pin "2") (pinfunction "CRED_2") (pintype "passive"))
      (node (ref "LED56") (pin "2") (pinfunction "CRED_2") (pintype "passive"))
      (node (ref "LED72") (pin "2") (pinfunction "CRED_2") (pintype "passive"))
      (node (ref "LED8") (pin "2") (pinfunction "CRED_2") (pintype "passive"))
      (node (ref "LED88") (pin "2") (pinfunction "CRED_2") (pintype "passive"))
    )
    (net (code "41") (name "/R8") (class "Default")
      (node (ref "LED105") (pin "2") (pinfunction "CRED_2") (pintype "passive"))
      (node (ref "LED121") (pin "2") (pinfunction "CRED_2") (pintype "passive"))
      (node (ref "LED137") (pin "2") (pinfunction "CRED_2") (pintype "passive"))
      (node (ref "LED153") (pin "2") (pinfunction "CRED_2") (pintype "passive"))
      (node (ref "LED169") (pin "2") (pinfunction "CRED_2") (pintype "passive"))
      (node (ref "LED185") (pin "2") (pinfunction "CRED_2") (pintype "passive"))
      (node (ref "LED201") (pin "2") (pinfunction "CRED_2") (pintype "passive"))
      (node (ref "LED217") (pin "2") (pinfunction "CRED_2") (pintype "passive"))
      (node (ref "LED233") (pin "2") (pinfunction "CRED_2") (pintype "passive"))
      (node (ref "LED249") (pin "2") (pinfunction "CRED_2") (pintype "passive"))
      (node (ref "LED25") (pin "2") (pinfunction "CRED_2") (pintype "passive"))
      (node (ref "LED41") (pin "2") (pinfunction "CRED_2") (pintype "passive"))
      (node (ref "LED57") (pin "2") (pinfunction "CRED_2") (pintype "passive"))
      (node (ref "LED73") (pin "2") (pinfunction "CRED_2") (pintype "passive"))
      (node (ref "LED89") (pin "2") (pinfunction "CRED_2") (pintype "passive"))
      (node (ref "LED9") (pin "2") (pinfunction "CRED_2") (pintype "passive"))
    )
    (net (code "42") (name "/R9") (class "Default")
      (node (ref "LED10") (pin "2") (pinfunction "CRED_2") (pintype "passive"))
      (node (ref "LED106") (pin "2") (pinfunction "CRED_2") (pintype "passive"))
      (node (ref "LED122") (pin "2") (pinfunction "CRED_2") (pintype "passive"))
      (node (ref "LED138") (pin "2") (pinfunction "CRED_2") (pintype "passive"))
      (node (ref "LED154") (pin "2") (pinfunction "CRED_2") (pintype "passive"))
      (node (ref "LED170") (pin "2") (pinfunction "CRED_2") (pintype "passive"))
      (node (ref "LED186") (pin "2") (pinfunction "CRED_2") (pintype "passive"))
      (node (ref "LED202") (pin "2") (pinfunction "CRED_2") (pintype "passive"))
      (node (ref "LED218") (pin "2") (pinfunction "CRED_2") (pintype "passive"))
      (node (ref "LED234") (pin "2") (pinfunction "CRED_2") (pintype "passive"))
      (node (ref "LED250") (pin "2") (pinfunction "CRED_2") (pintype "passive"))
      (node (ref "LED26") (pin "2") (pinfunction "CRED_2") (pintype "passive"))
      (node (ref "LED42") (pin "2") (pinfunction "CRED_2") (pintype "passive"))
      (node (ref "LED58") (pin "2") (pinfunction "CRED_2") (pintype "passive"))
      (node (ref "LED74") (pin "2") (pinfunction "CRED_2") (pintype "passive"))
      (node (ref "LED90") (pin "2") (pinfunction "CRED_2") (pintype "passive"))
    )
    (net (code "43") (name "/R10") (class "Default")
      (node (ref "LED107") (pin "2") (pinfunction "CRED_2") (pintype "passive"))
      (node (ref "LED11") (pin "2") (pinfunction "CRED_2") (pintype "passive"))
      (node (ref "LED123") (pin "2") (pinfunction "CRED_2") (pintype "passive"))
      (node (ref "LED139") (pin "2") (pinfunction "CRED_2") (pintype "passive"))
      (node (ref "LED155") (pin "2") (pinfunction "CRED_2") (pintype "passive"))
      (node (ref "LED171") (pin "2") (pinfunction "CRED_2") (pintype "passive"))
      (node (ref "LED187") (pin "2") (pinfunction "CRED_2") (pintype "passive"))
      (node (ref "LED203") (pin "2") (pinfunction "CRED_2") (pintype "passive"))
      (node (ref "LED219") (pin "2") (pinfunction "CRED_2") (pintype "passive"))
      (node (ref "LED235") (pin "2") (pinfunction "CRED_2") (pintype "passive"))
      (node (ref "LED251") (pin "2") (pinfunction "CRED_2") (pintype "passive"))
      (node (ref "LED27") (pin "2") (pinfunction "CRED_2") (pintype "passive"))
      (node (ref "LED43") (pin "2") (pinfunction "CRED_2") (pintype "passive"))
      (node (ref "LED59") (pin "2") (pinfunction "CRED_2") (pintype "passive"))
      (node (ref "LED75") (pin "2") (pinfunction "CRED_2") (pintype "passive"))
      (node (ref "LED91") (pin "2") (pinfunction "CRED_2") (pintype "passive"))
    )
    (net (code "44") (name "/R11") (class "Default")
      (node (ref "LED108") (pin "2") (pinfunction "CRED_2") (pintype "passive"))
      (node (ref "LED12") (pin "2") (pinfunction "CRED_2") (pintype "passive"))
      (node (ref "LED124") (pin "2") (pinfunction "CRED_2") (pintype "passive"))
      (node (ref "LED140") (pin "2") (pinfunction "CRED_2") (pintype "passive"))
      (node (ref "LED156") (pin "2") (pinfunction "CRED_2") (pintype "passive"))
      (node (ref "LED172") (pin "2") (pinfunction "CRED_2") (pintype "passive"))
      (node (ref "LED188") (pin "2") (pinfunction "CRED_2") (pintype "passive"))
      (node (ref "LED204") (pin "2") (pinfunction "CRED_2") (pintype "passive"))
      (node (ref "LED220") (pin "2") (pinfunction "CRED_2") (pintype "passive"))
      (node (ref "LED236") (pin "2") (pinfunction "CRED_2") (pintype "passive"))
      (node (ref "LED252") (pin "2") (pinfunction "CRED_2") (pintype "passive"))
      (node (ref "LED28") (pin "2") (pinfunction "CRED_2") (pintype "passive"))
      (node (ref "LED44") (pin "2") (pinfunction "CRED_2") (pintype "passive"))
      (node (ref "LED60") (pin "2") (pinfunction "CRED_2") (pintype "passive"))
      (node (ref "LED76") (pin "2") (pinfunction "CRED_2") (pintype "passive"))
      (node (ref "LED92") (pin "2") (pinfunction "CRED_2") (pintype "passive"))
    )
    (net (code "45") (name "/R12") (class "Default")
      (node (ref "LED109") (pin "2") (pinfunction "CRED_2") (pintype "passive"))
      (node (ref "LED125") (pin "2") (pinfunction "CRED_2") (pintype "passive"))
      (node (ref "LED13") (pin "2") (pinfunction "CRED_2") (pintype "passive"))
      (node (ref "LED141") (pin "2") (pinfunction "CRED_2") (pintype "passive"))
      (node (ref "LED157") (pin "2") (pinfunction "CRED_2") (pintype "passive"))
      (node (ref "LED173") (pin "2") (pinfunction "CRED_2") (pintype "passive"))
      (node (ref "LED189") (pin "2") (pinfunction "CRED_2") (pintype "passive"))
      (node (ref "LED205") (pin "2") (pinfunction "CRED_2") (pintype "passive"))
      (node (ref "LED221") (pin "2") (pinfunction "CRED_2") (pintype "passive"))
      (node (ref "LED237") (pin "2") (pinfunction "CRED_2") (pintype "passive"))
      (node (ref "LED253") (pin "2") (pinfunction "CRED_2") (pintype "passive"))
      (node (ref "LED29") (pin "2") (pinfunction "CRED_2") (pintype "passive"))
      (node (ref "LED45") (pin "2") (pinfunction "CRED_2") (pintype "passive"))
      (node (ref "LED61") (pin "2") (pinfunction "CRED_2") (pintype "passive"))
      (node (ref "LED77") (pin "2") (pinfunction "CRED_2") (pintype "passive"))
      (node (ref "LED93") (pin "2") (pinfunction "CRED_2") (pintype "passive"))
    )
    (net (code "46") (name "/R13") (class "Default")
      (node (ref "LED110") (pin "2") (pinfunction "CRED_2") (pintype "passive"))
      (node (ref "LED126") (pin "2") (pinfunction "CRED_2") (pintype "passive"))
      (node (ref "LED14") (pin "2") (pinfunction "CRED_2") (pintype "passive"))
      (node (ref "LED142") (pin "2") (pinfunction "CRED_2") (pintype "passive"))
      (node (ref "LED158") (pin "2") (pinfunction "CRED_2") (pintype "passive"))
      (node (ref "LED174") (pin "2") (pinfunction "CRED_2") (pintype "passive"))
      (node (ref "LED190") (pin "2") (pinfunction "CRED_2") (pintype "passive"))
      (node (ref "LED206") (pin "2") (pinfunction "CRED_2") (pintype "passive"))
      (node (ref "LED222") (pin "2") (pinfunction "CRED_2") (pintype "passive"))
      (node (ref "LED238") (pin "2") (pinfunction "CRED_2") (pintype "passive"))
      (node (ref "LED254") (pin "2") (pinfunction "CRED_2") (pintype "passive"))
      (node (ref "LED30") (pin "2") (pinfunction "CRED_2") (pintype "passive"))
      (node (ref "LED46") (pin "2") (pinfunction "CRED_2") (pintype "passive"))
      (node (ref "LED62") (pin "2") (pinfunction "CRED_2") (pintype "passive"))
      (node (ref "LED78") (pin "2") (pinfunction "CRED_2") (pintype "passive"))
      (node (ref "LED94") (pin "2") (pinfunction "CRED_2") (pintype "passive"))
    )
    (net (code "47") (name "/R14") (class "Default")
      (node (ref "LED111") (pin "2") (pinfunction "CRED_2") (pintype "passive"))
      (node (ref "LED127") (pin "2") (pinfunction "CRED_2") (pintype "passive"))
      (node (ref "LED143") (pin "2") (pinfunction "CRED_2") (pintype "passive"))
      (node (ref "LED15") (pin "2") (pinfunction "CRED_2") (pintype "passive"))
      (node (ref "LED159") (pin "2") (pinfunction "CRED_2") (pintype "passive"))
      (node (ref "LED175") (pin "2") (pinfunction "CRED_2") (pintype "passive"))
      (node (ref "LED191") (pin "2") (pinfunction "CRED_2") (pintype "passive"))
      (node (ref "LED207") (pin "2") (pinfunction "CRED_2") (pintype "passive"))
      (node (ref "LED223") (pin "2") (pinfunction "CRED_2") (pintype "passive"))
      (node (ref "LED239") (pin "2") (pinfunction "CRED_2") (pintype "passive"))
      (node (ref "LED255") (pin "2") (pinfunction "CRED_2") (pintype "passive"))
      (node (ref "LED31") (pin "2") (pinfunction "CRED_2") (pintype "passive"))
      (node (ref "LED47") (pin "2") (pinfunction "CRED_2") (pintype "passive"))
      (node (ref "LED63") (pin "2") (pinfunction "CRED_2") (pintype "passive"))
      (node (ref "LED79") (pin "2") (pinfunction "CRED_2") (pintype "passive"))
      (node (ref "LED95") (pin "2") (pinfunction "CRED_2") (pintype "passive"))
    )
    (net (code "48") (name "/R15") (class "Default")
      (node (ref "LED112") (pin "2") (pinfunction "CRED_2") (pintype "passive"))
      (node (ref "LED128") (pin "2") (pinfunction "CRED_2") (pintype "passive"))
      (node (ref "LED144") (pin "2") (pinfunction "CRED_2") (pintype "passive"))
      (node (ref "LED16") (pin "2") (pinfunction "CRED_2") (pintype "passive"))
      (node (ref "LED160") (pin "2") (pinfunction "CRED_2") (pintype "passive"))
      (node (ref "LED176") (pin "2") (pinfunction "CRED_2") (pintype "passive"))
      (node (ref "LED192") (pin "2") (pinfunction "CRED_2") (pintype "passive"))
      (node (ref "LED208") (pin "2") (pinfunction "CRED_2") (pintype "passive"))
      (node (ref "LED224") (pin "2") (pinfunction "CRED_2") (pintype "passive"))
      (node (ref "LED240") (pin "2") (pinfunction "CRED_2") (pintype "passive"))
      (node (ref "LED256") (pin "2") (pinfunction "CRED_2") (pintype "passive"))
      (node (ref "LED32") (pin "2") (pinfunction "CRED_2") (pintype "passive"))
      (node (ref "LED48") (pin "2") (pinfunction "CRED_2") (pintype "passive"))
      (node (ref "LED64") (pin "2") (pinfunction "CRED_2") (pintype "passive"))
      (node (ref "LED80") (pin "2") (pinfunction "CRED_2") (pintype "passive"))
      (node (ref "LED96") (pin "2") (pinfunction "CRED_2") (pintype "passive"))
    )
    (net (code "49") (name "/Y0") (class "Default")
      (node (ref "LED1") (pin "4") (pinfunction "A_4") (pintype "passive"))
      (node (ref "LED10") (pin "4") (pinfunction "A_4") (pintype "passive"))
      (node (ref "LED11") (pin "4") (pinfunction "A_4") (pintype "passive"))
      (node (ref "LED12") (pin "4") (pinfunction "A_4") (pintype "passive"))
      (node (ref "LED13") (pin "4") (pinfunction "A_4") (pintype "passive"))
      (node (ref "LED14") (pin "4") (pinfunction "A_4") (pintype "passive"))
      (node (ref "LED15") (pin "4") (pinfunction "A_4") (pintype "passive"))
      (node (ref "LED16") (pin "4") (pinfunction "A_4") (pintype "passive"))
      (node (ref "LED2") (pin "4") (pinfunction "A_4") (pintype "passive"))
      (node (ref "LED3") (pin "4") (pinfunction "A_4") (pintype "passive"))
      (node (ref "LED4") (pin "4") (pinfunction "A_4") (pintype "passive"))
      (node (ref "LED5") (pin "4") (pinfunction "A_4") (pintype "passive"))
      (node (ref "LED6") (pin "4") (pinfunction "A_4") (pintype "passive"))
      (node (ref "LED7") (pin "4") (pinfunction "A_4") (pintype "passive"))
      (node (ref "LED8") (pin "4") (pinfunction "A_4") (pintype "passive"))
      (node (ref "LED9") (pin "4") (pinfunction "A_4") (pintype "passive"))
    )
    (net (code "50") (name "/Y1") (class "Default")
      (node (ref "LED17") (pin "4") (pinfunction "A_4") (pintype "passive"))
      (node (ref "LED18") (pin "4") (pinfunction "A_4") (pintype "passive"))
      (node (ref "LED19") (pin "4") (pinfunction "A_4") (pintype "passive"))
      (node (ref "LED20") (pin "4") (pinfunction "A_4") (pintype "passive"))
      (node (ref "LED21") (pin "4") (pinfunction "A_4") (pintype "passive"))
      (node (ref "LED22") (pin "4") (pinfunction "A_4") (pintype "passive"))
      (node (ref "LED23") (pin "4") (pinfunction "A_4") (pintype "passive"))
      (node (ref "LED24") (pin "4") (pinfunction "A_4") (pintype "passive"))
      (node (ref "LED25") (pin "4") (pinfunction "A_4") (pintype "passive"))
      (node (ref "LED26") (pin "4") (pinfunction "A_4") (pintype "passive"))
      (node (ref "LED27") (pin "4") (pinfunction "A_4") (pintype "passive"))
      (node (ref "LED28") (pin "4") (pinfunction "A_4") (pintype "passive"))
      (node (ref "LED29") (pin "4") (pinfunction "A_4") (pintype "passive"))
      (node (ref "LED30") (pin "4") (pinfunction "A_4") (pintype "passive"))
      (node (ref "LED31") (pin "4") (pinfunction "A_4") (pintype "passive"))
      (node (ref "LED32") (pin "4") (pinfunction "A_4") (pintype "passive"))
    )
    (net (code "51") (name "/Y2") (class "Default")
      (node (ref "LED33") (pin "4") (pinfunction "A_4") (pintype "passive"))
      (node (ref "LED34") (pin "4") (pinfunction "A_4") (pintype "passive"))
      (node (ref "LED35") (pin "4") (pinfunction "A_4") (pintype "passive"))
      (node (ref "LED36") (pin "4") (pinfunction "A_4") (pintype "passive"))
      (node (ref "LED37") (pin "4") (pinfunction "A_4") (pintype "passive"))
      (node (ref "LED38") (pin "4") (pinfunction "A_4") (pintype "passive"))
      (node (ref "LED39") (pin "4") (pinfunction "A_4") (pintype "passive"))
      (node (ref "LED40") (pin "4") (pinfunction "A_4") (pintype "passive"))
      (node (ref "LED41") (pin "4") (pinfunction "A_4") (pintype "passive"))
      (node (ref "LED42") (pin "4") (pinfunction "A_4") (pintype "passive"))
      (node (ref "LED43") (pin "4") (pinfunction "A_4") (pintype "passive"))
      (node (ref "LED44") (pin "4") (pinfunction "A_4") (pintype "passive"))
      (node (ref "LED45") (pin "4") (pinfunction "A_4") (pintype "passive"))
      (node (ref "LED46") (pin "4") (pinfunction "A_4") (pintype "passive"))
      (node (ref "LED47") (pin "4") (pinfunction "A_4") (pintype "passive"))
      (node (ref "LED48") (pin "4") (pinfunction "A_4") (pintype "passive"))
    )
    (net (code "52") (name "/Y3") (class "Default")
      (node (ref "LED49") (pin "4") (pinfunction "A_4") (pintype "passive"))
      (node (ref "LED50") (pin "4") (pinfunction "A_4") (pintype "passive"))
      (node (ref "LED51") (pin "4") (pinfunction "A_4") (pintype "passive"))
      (node (ref "LED52") (pin "4") (pinfunction "A_4") (pintype "passive"))
      (node (ref "LED53") (pin "4") (pinfunction "A_4") (pintype "passive"))
      (node (ref "LED54") (pin "4") (pinfunction "A_4") (pintype "passive"))
      (node (ref "LED55") (pin "4") (pinfunction "A_4") (pintype "passive"))
      (node (ref "LED56") (pin "4") (pinfunction "A_4") (pintype "passive"))
      (node (ref "LED57") (pin "4") (pinfunction "A_4") (pintype "passive"))
      (node (ref "LED58") (pin "4") (pinfunction "A_4") (pintype "passive"))
      (node (ref "LED59") (pin "4") (pinfunction "A_4") (pintype "passive"))
      (node (ref "LED60") (pin "4") (pinfunction "A_4") (pintype "passive"))
      (node (ref "LED61") (pin "4") (pinfunction "A_4") (pintype "passive"))
      (node (ref "LED62") (pin "4") (pinfunction "A_4") (pintype "passive"))
      (node (ref "LED63") (pin "4") (pinfunction "A_4") (pintype "passive"))
      (node (ref "LED64") (pin "4") (pinfunction "A_4") (pintype "passive"))
    )
    (net (code "53") (name "/Y4") (class "Default")
      (node (ref "LED65") (pin "4") (pinfunction "A_4") (pintype "passive"))
      (node (ref "LED66") (pin "4") (pinfunction "A_4") (pintype "passive"))
      (node (ref "LED67") (pin "4") (pinfunction "A_4") (pintype "passive"))
      (node (ref "LED68") (pin "4") (pinfunction "A_4") (pintype "passive"))
      (node (ref "LED69") (pin "4") (pinfunction "A_4") (pintype "passive"))
      (node (ref "LED70") (pin "4") (pinfunction "A_4") (pintype "passive"))
      (node (ref "LED71") (pin "4") (pinfunction "A_4") (pintype "passive"))
      (node (ref "LED72") (pin "4") (pinfunction "A_4") (pintype "passive"))
      (node (ref "LED73") (pin "4") (pinfunction "A_4") (pintype "passive"))
      (node (ref "LED74") (pin "4") (pinfunction "A_4") (pintype "passive"))
      (node (ref "LED75") (pin "4") (pinfunction "A_4") (pintype "passive"))
      (node (ref "LED76") (pin "4") (pinfunction "A_4") (pintype "passive"))
      (node (ref "LED77") (pin "4") (pinfunction "A_4") (pintype "passive"))
      (node (ref "LED78") (pin "4") (pinfunction "A_4") (pintype "passive"))
      (node (ref "LED79") (pin "4") (pinfunction "A_4") (pintype "passive"))
      (node (ref "LED80") (pin "4") (pinfunction "A_4") (pintype "passive"))
    )
    (net (code "54") (name "/Y5") (class "Default")
      (node (ref "LED81") (pin "4") (pinfunction "A_4") (pintype "passive"))
      (node (ref "LED82") (pin "4") (pinfunction "A_4") (pintype "passive"))
      (node (ref "LED83") (pin "4") (pinfunction "A_4") (pintype "passive"))
      (node (ref "LED84") (pin "4") (pinfunction "A_4") (pintype "passive"))
      (node (ref "LED85") (pin "4") (pinfunction "A_4") (pintype "passive"))
      (node (ref "LED86") (pin "4") (pinfunction "A_4") (pintype "passive"))
      (node (ref "LED87") (pin "4") (pinfunction "A_4") (pintype "passive"))
      (node (ref "LED88") (pin "4") (pinfunction "A_4") (pintype "passive"))
      (node (ref "LED89") (pin "4") (pinfunction "A_4") (pintype "passive"))
      (node (ref "LED90") (pin "4") (pinfunction "A_4") (pintype "passive"))
      (node (ref "LED91") (pin "4") (pinfunction "A_4") (pintype "passive"))
      (node (ref "LED92") (pin "4") (pinfunction "A_4") (pintype "passive"))
      (node (ref "LED93") (pin "4") (pinfunction "A_4") (pintype "passive"))
      (node (ref "LED94") (pin "4") (pinfunction "A_4") (pintype "passive"))
      (node (ref "LED95") (pin "4") (pinfunction "A_4") (pintype "passive"))
      (node (ref "LED96") (pin "4") (pinfunction "A_4") (pintype "passive"))
    )
    (net (code "55") (name "/Y6") (class "Default")
      (node (ref "LED100") (pin "4") (pinfunction "A_4") (pintype "passive"))
      (node (ref "LED101") (pin "4") (pinfunction "A_4") (pintype "passive"))
      (node (ref "LED102") (pin "4") (pinfunction "A_4") (pintype "passive"))
      (node (ref "LED103") (pin "4") (pinfunction "A_4") (pintype "passive"))
      (node (ref "LED104") (pin "4") (pinfunction "A_4") (pintype "passive"))
      (node (ref "LED105") (pin "4") (pinfunction "A_4") (pintype "passive"))
      (node (ref "LED106") (pin "4") (pinfunction "A_4") (pintype "passive"))
      (node (ref "LED107") (pin "4") (pinfunction "A_4") (pintype "passive"))
      (node (ref "LED108") (pin "4") (pinfunction "A_4") (pintype "passive"))
      (node (ref "LED109") (pin "4") (pinfunction "A_4") (pintype "passive"))
      (node (ref "LED110") (pin "4") (pinfunction "A_4") (pintype "passive"))
      (node (ref "LED111") (pin "4") (pinfunction "A_4") (pintype "passive"))
      (node (ref "LED112") (pin "4") (pinfunction "A_4") (pintype "passive"))
      (node (ref "LED97") (pin "4") (pinfunction "A_4") (pintype "passive"))
      (node (ref "LED98") (pin "4") (pinfunction "A_4") (pintype "passive"))
      (node (ref "LED99") (pin "4") (pinfunction "A_4") (pintype "passive"))
    )
    (net (code "56") (name "/Y7") (class "Default")
      (node (ref "LED113") (pin "4") (pinfunction "A_4") (pintype "passive"))
      (node (ref "LED114") (pin "4") (pinfunction "A_4") (pintype "passive"))
      (node (ref "LED115") (pin "4") (pinfunction "A_4") (pintype "passive"))
      (node (ref "LED116") (pin "4") (pinfunction "A_4") (pintype "passive"))
      (node (ref "LED117") (pin "4") (pinfunction "A_4") (pintype "passive"))
      (node (ref "LED118") (pin "4") (pinfunction "A_4") (pintype "passive"))
      (node (ref "LED119") (pin "4") (pinfunction "A_4") (pintype "passive"))
      (node (ref "LED120") (pin "4") (pinfunction "A_4") (pintype "passive"))
      (node (ref "LED121") (pin "4") (pinfunction "A_4") (pintype "passive"))
      (node (ref "LED122") (pin "4") (pinfunction "A_4") (pintype "passive"))
      (node (ref "LED123") (pin "4") (pinfunction "A_4") (pintype "passive"))
      (node (ref "LED124") (pin "4") (pinfunction "A_4") (pintype "passive"))
      (node (ref "LED125") (pin "4") (pinfunction "A_4") (pintype "passive"))
      (node (ref "LED126") (pin "4") (pinfunction "A_4") (pintype "passive"))
      (node (ref "LED127") (pin "4") (pinfunction "A_4") (pintype "passive"))
      (node (ref "LED128") (pin "4") (pinfunction "A_4") (pintype "passive"))
    )
    (net (code "57") (name "/Y8") (class "Default")
      (node (ref "LED129") (pin "4") (pinfunction "A_4") (pintype "passive"))
      (node (ref "LED130") (pin "4") (pinfunction "A_4") (pintype "passive"))
      (node (ref "LED131") (pin "4") (pinfunction "A_4") (pintype "passive"))
      (node (ref "LED132") (pin "4") (pinfunction "A_4") (pintype "passive"))
      (node (ref "LED133") (pin "4") (pinfunction "A_4") (pintype "passive"))
      (node (ref "LED134") (pin "4") (pinfunction "A_4") (pintype "passive"))
      (node (ref "LED135") (pin "4") (pinfunction "A_4") (pintype "passive"))
      (node (ref "LED136") (pin "4") (pinfunction "A_4") (pintype "passive"))
      (node (ref "LED137") (pin "4") (pinfunction "A_4") (pintype "passive"))
      (node (ref "LED138") (pin "4") (pinfunction "A_4") (pintype "passive"))
      (node (ref "LED139") (pin "4") (pinfunction "A_4") (pintype "passive"))
      (node (ref "LED140") (pin "4") (pinfunction "A_4") (pintype "passive"))
      (node (ref "LED141") (pin "4") (pinfunction "A_4") (pintype "passive"))
      (node (ref "LED142") (pin "4") (pinfunction "A_4") (pintype "passive"))
      (node (ref "LED143") (pin "4") (pinfunction "A_4") (pintype "passive"))
      (node (ref "LED144") (pin "4") (pinfunction "A_4") (pintype "passive"))
    )
    (net (code "58") (name "/Y9") (class "Default")
      (node (ref "LED145") (pin "4") (pinfunction "A_4") (pintype "passive"))
      (node (ref "LED146") (pin "4") (pinfunction "A_4") (pintype "passive"))
      (node (ref "LED147") (pin "4") (pinfunction "A_4") (pintype "passive"))
      (node (ref "LED148") (pin "4") (pinfunction "A_4") (pintype "passive"))
      (node (ref "LED149") (pin "4") (pinfunction "A_4") (pintype "passive"))
      (node (ref "LED150") (pin "4") (pinfunction "A_4") (pintype "passive"))
      (node (ref "LED151") (pin "4") (pinfunction "A_4") (pintype "passive"))
      (node (ref "LED152") (pin "4") (pinfunction "A_4") (pintype "passive"))
      (node (ref "LED153") (pin "4") (pinfunction "A_4") (pintype "passive"))
      (node (ref "LED154") (pin "4") (pinfunction "A_4") (pintype "passive"))
      (node (ref "LED155") (pin "4") (pinfunction "A_4") (pintype "passive"))
      (node (ref "LED156") (pin "4") (pinfunction "A_4") (pintype "passive"))
      (node (ref "LED157") (pin "4") (pinfunction "A_4") (pintype "passive"))
      (node (ref "LED158") (pin "4") (pinfunction "A_4") (pintype "passive"))
      (node (ref "LED159") (pin "4") (pinfunction "A_4") (pintype "passive"))
      (node (ref "LED160") (pin "4") (pinfunction "A_4") (pintype "passive"))
    )
    (net (code "59") (name "/Y10") (class "Default")
      (node (ref "LED161") (pin "4") (pinfunction "A_4") (pintype "passive"))
      (node (ref "LED162") (pin "4") (pinfunction "A_4") (pintype "passive"))
      (node (ref "LED163") (pin "4") (pinfunction "A_4") (pintype "passive"))
      (node (ref "LED164") (pin "4") (pinfunction "A_4") (pintype "passive"))
      (node (ref "LED165") (pin "4") (pinfunction "A_4") (pintype "passive"))
      (node (ref "LED166") (pin "4") (pinfunction "A_4") (pintype "passive"))
      (node (ref "LED167") (pin "4") (pinfunction "A_4") (pintype "passive"))
      (node (ref "LED168") (pin "4") (pinfunction "A_4") (pintype "passive"))
      (node (ref "LED169") (pin "4") (pinfunction "A_4") (pintype "passive"))
      (node (ref "LED170") (pin "4") (pinfunction "A_4") (pintype "passive"))
      (node (ref "LED171") (pin "4") (pinfunction "A_4") (pintype "passive"))
      (node (ref "LED172") (pin "4") (pinfunction "A_4") (pintype "passive"))
      (node (ref "LED173") (pin "4") (pinfunction "A_4") (pintype "passive"))
      (node (ref "LED174") (pin "4") (pinfunction "A_4") (pintype "passive"))
      (node (ref "LED175") (pin "4") (pinfunction "A_4") (pintype "passive"))
      (node (ref "LED176") (pin "4") (pinfunction "A_4") (pintype "passive"))
    )
    (net (code "60") (name "/Y11") (class "Default")
      (node (ref "LED177") (pin "4") (pinfunction "A_4") (pintype "passive"))
      (node (ref "LED178") (pin "4") (pinfunction "A_4") (pintype "passive"))
      (node (ref "LED179") (pin "4") (pinfunction "A_4") (pintype "passive"))
      (node (ref "LED180") (pin "4") (pinfunction "A_4") (pintype "passive"))
      (node (ref "LED181") (pin "4") (pinfunction "A_4") (pintype "passive"))
      (node (ref "LED182") (pin "4") (pinfunction "A_4") (pintype "passive"))
      (node (ref "LED183") (pin "4") (pinfunction "A_4") (pintype "passive"))
      (node (ref "LED184") (pin "4") (pinfunction "A_4") (pintype "passive"))
      (node (ref "LED185") (pin "4") (pinfunction "A_4") (pintype "passive"))
      (node (ref "LED186") (pin "4") (pinfunction "A_4") (pintype "passive"))
      (node (ref "LED187") (pin "4") (pinfunction "A_4") (pintype "passive"))
      (node (ref "LED188") (pin "4") (pinfunction "A_4") (pintype "passive"))
      (node (ref "LED189") (pin "4") (pinfunction "A_4") (pintype "passive"))
      (node (ref "LED190") (pin "4") (pinfunction "A_4") (pintype "passive"))
      (node (ref "LED191") (pin "4") (pinfunction "A_4") (pintype "passive"))
      (node (ref "LED192") (pin "4") (pinfunction "A_4") (pintype "passive"))
    )
    (net (code "61") (name "/Y12") (class "Default")
      (node (ref "LED193") (pin "4") (pinfunction "A_4") (pintype "passive"))
      (node (ref "LED194") (pin "4") (pinfunction "A_4") (pintype "passive"))
      (node (ref "LED195") (pin "4") (pinfunction "A_4") (pintype "passive"))
      (node (ref "LED196") (pin "4") (pinfunction "A_4") (pintype "passive"))
      (node (ref "LED197") (pin "4") (pinfunction "A_4") (pintype "passive"))
      (node (ref "LED198") (pin "4") (pinfunction "A_4") (pintype "passive"))
      (node (ref "LED199") (pin "4") (pinfunction "A_4") (pintype "passive"))
      (node (ref "LED200") (pin "4") (pinfunction "A_4") (pintype "passive"))
      (node (ref "LED201") (pin "4") (pinfunction "A_4") (pintype "passive"))
      (node (ref "LED202") (pin "4") (pinfunction "A_4") (pintype "passive"))
      (node (ref "LED203") (pin "4") (pinfunction "A_4") (pintype "passive"))
      (node (ref "LED204") (pin "4") (pinfunction "A_4") (pintype "passive"))
      (node (ref "LED205") (pin "4") (pinfunction "A_4") (pintype "passive"))
      (node (ref "LED206") (pin "4") (pinfunction "A_4") (pintype "passive"))
      (node (ref "LED207") (pin "4") (pinfunction "A_4") (pintype "passive"))
      (node (ref "LED208") (pin "4") (pinfunction "A_4") (pintype "passive"))
    )
    (net (code "62") (name "/Y13") (class "Default")
      (node (ref "LED209") (pin "4") (pinfunction "A_4") (pintype "passive"))
      (node (ref "LED210") (pin "4") (pinfunction "A_4") (pintype "passive"))
      (node (ref "LED211") (pin "4") (pinfunction "A_4") (pintype "passive"))
      (node (ref "LED212") (pin "4") (pinfunction "A_4") (pintype "passive"))
      (node (ref "LED213") (pin "4") (pinfunction "A_4") (pintype "passive"))
      (node (ref "LED214") (pin "4") (pinfunction "A_4") (pintype "passive"))
      (node (ref "LED215") (pin "4") (pinfunction "A_4") (pintype "passive"))
      (node (ref "LED216") (pin "4") (pinfunction "A_4") (pintype "passive"))
      (node (ref "LED217") (pin "4") (pinfunction "A_4") (pintype "passive"))
      (node (ref "LED218") (pin "4") (pinfunction "A_4") (pintype "passive"))
      (node (ref "LED219") (pin "4") (pinfunction "A_4") (pintype "passive"))
      (node (ref "LED220") (pin "4") (pinfunction "A_4") (pintype "passive"))
      (node (ref "LED221") (pin "4") (pinfunction "A_4") (pintype "passive"))
      (node (ref "LED222") (pin "4") (pinfunction "A_4") (pintype "passive"))
      (node (ref "LED223") (pin "4") (pinfunction "A_4") (pintype "passive"))
      (node (ref "LED224") (pin "4") (pinfunction "A_4") (pintype "passive"))
    )
    (net (code "63") (name "/Y14") (class "Default")
      (node (ref "LED225") (pin "4") (pinfunction "A_4") (pintype "passive"))
      (node (ref "LED226") (pin "4") (pinfunction "A_4") (pintype "passive"))
      (node (ref "LED227") (pin "4") (pinfunction "A_4") (pintype "passive"))
      (node (ref "LED228") (pin "4") (pinfunction "A_4") (pintype "passive"))
      (node (ref "LED229") (pin "4") (pinfunction "A_4") (pintype "passive"))
      (node (ref "LED230") (pin "4") (pinfunction "A_4") (pintype "passive"))
      (node (ref "LED231") (pin "4") (pinfunction "A_4") (pintype "passive"))
      (node (ref "LED232") (pin "4") (pinfunction "A_4") (pintype "passive"))
      (node (ref "LED233") (pin "4") (pinfunction "A_4") (pintype "passive"))
      (node (ref "LED234") (pin "4") (pinfunction "A_4") (pintype "passive"))
      (node (ref "LED235") (pin "4") (pinfunction "A_4") (pintype "passive"))
      (node (ref "LED236") (pin "4") (pinfunction "A_4") (pintype "passive"))
      (node (ref "LED237") (pin "4") (pinfunction "A_4") (pintype "passive"))
      (node (ref "LED238") (pin "4") (pinfunction "A_4") (pintype "passive"))
      (node (ref "LED239") (pin "4") (pinfunction "A_4") (pintype "passive"))
      (node (ref "LED240") (pin "4") (pinfunction "A_4") (pintype "passive"))
    )
    (net (code "64") (name "/Y15") (class "Default")
      (node (ref "LED241") (pin "4") (pinfunction "A_4") (pintype "passive"))
      (node (ref "LED242") (pin "4") (pinfunction "A_4") (pintype "passive"))
      (node (ref "LED243") (pin "4") (pinfunction "A_4") (pintype "passive"))
      (node (ref "LED244") (pin "4") (pinfunction "A_4") (pintype "passive"))
      (node (ref "LED245") (pin "4") (pinfunction "A_4") (pintype "passive"))
      (node (ref "LED246") (pin "4") (pinfunction "A_4") (pintype "passive"))
      (node (ref "LED247") (pin "4") (pinfunction "A_4") (pintype "passive"))
      (node (ref "LED248") (pin "4") (pinfunction "A_4") (pintype "passive"))
      (node (ref "LED249") (pin "4") (pinfunction "A_4") (pintype "passive"))
      (node (ref "LED250") (pin "4") (pinfunction "A_4") (pintype "passive"))
      (node (ref "LED251") (pin "4") (pinfunction "A_4") (pintype "passive"))
      (node (ref "LED252") (pin "4") (pinfunction "A_4") (pintype "passive"))
      (node (ref "LED253") (pin "4") (pinfunction "A_4") (pintype "passive"))
      (node (ref "LED254") (pin "4") (pinfunction "A_4") (pintype "passive"))
      (node (ref "LED255") (pin "4") (pinfunction "A_4") (pintype "passive"))
      (node (ref "LED256") (pin "4") (pinfunction "A_4") (pintype "passive"))
    )
  )
)
